# QI9-2604-A01.net
KiCad netlist of a schematic drawn in Altium Designer
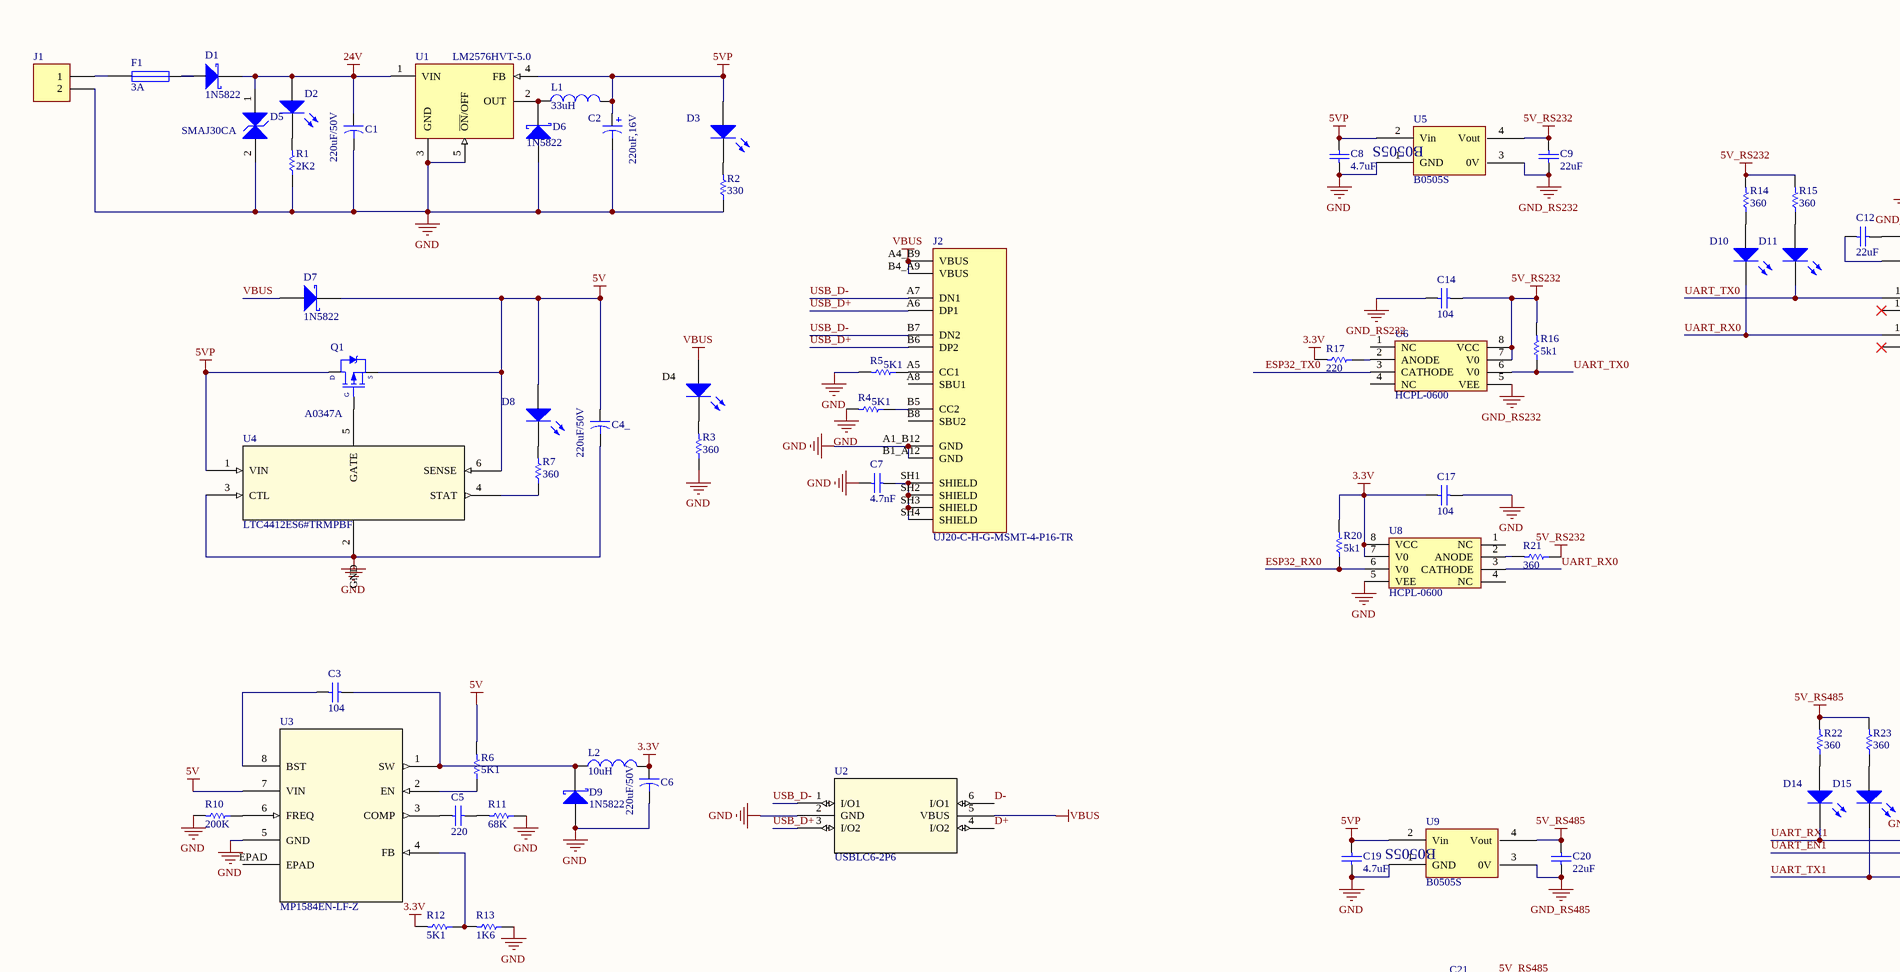
[diagram p0: QI9-2604-A01.SchDoc, top left]
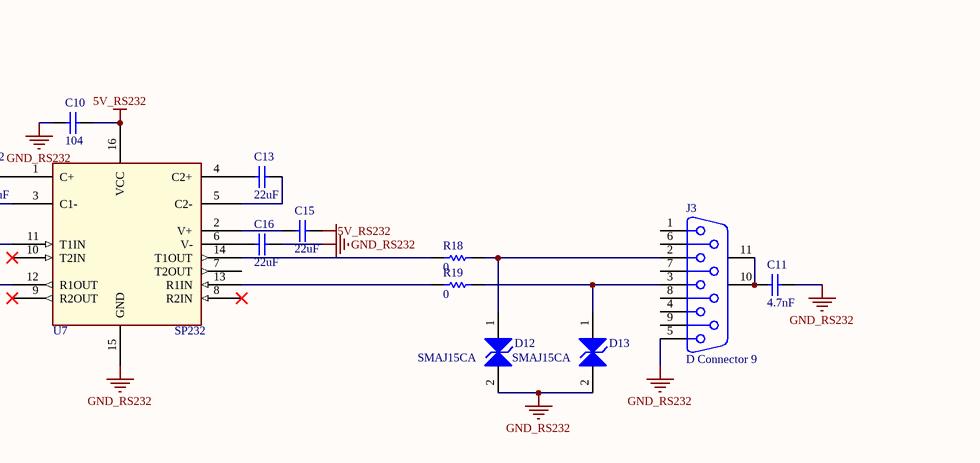
[diagram p1: QI9-2604-A01.SchDoc, top right]
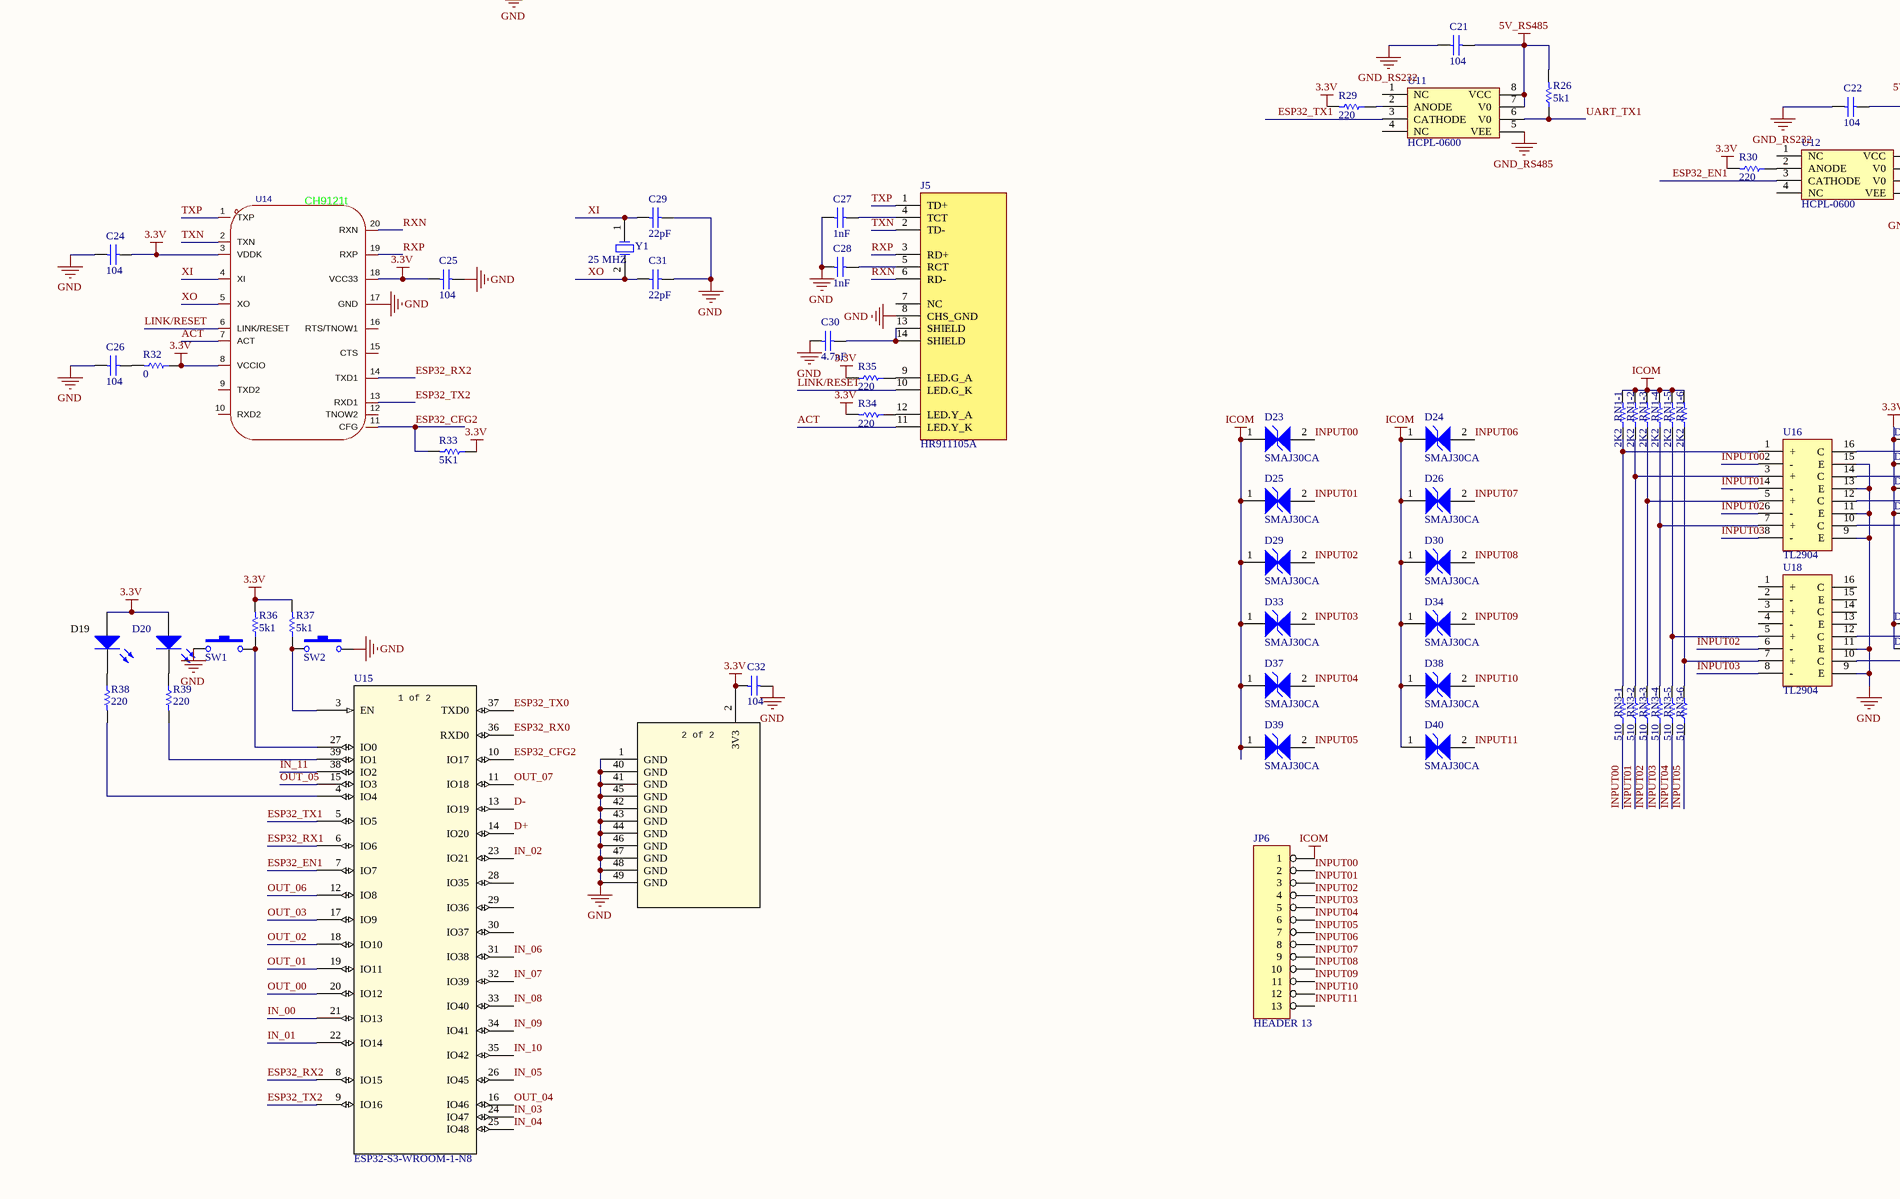
[diagram p2: QI9-2604-A01.SchDoc, bottom left]
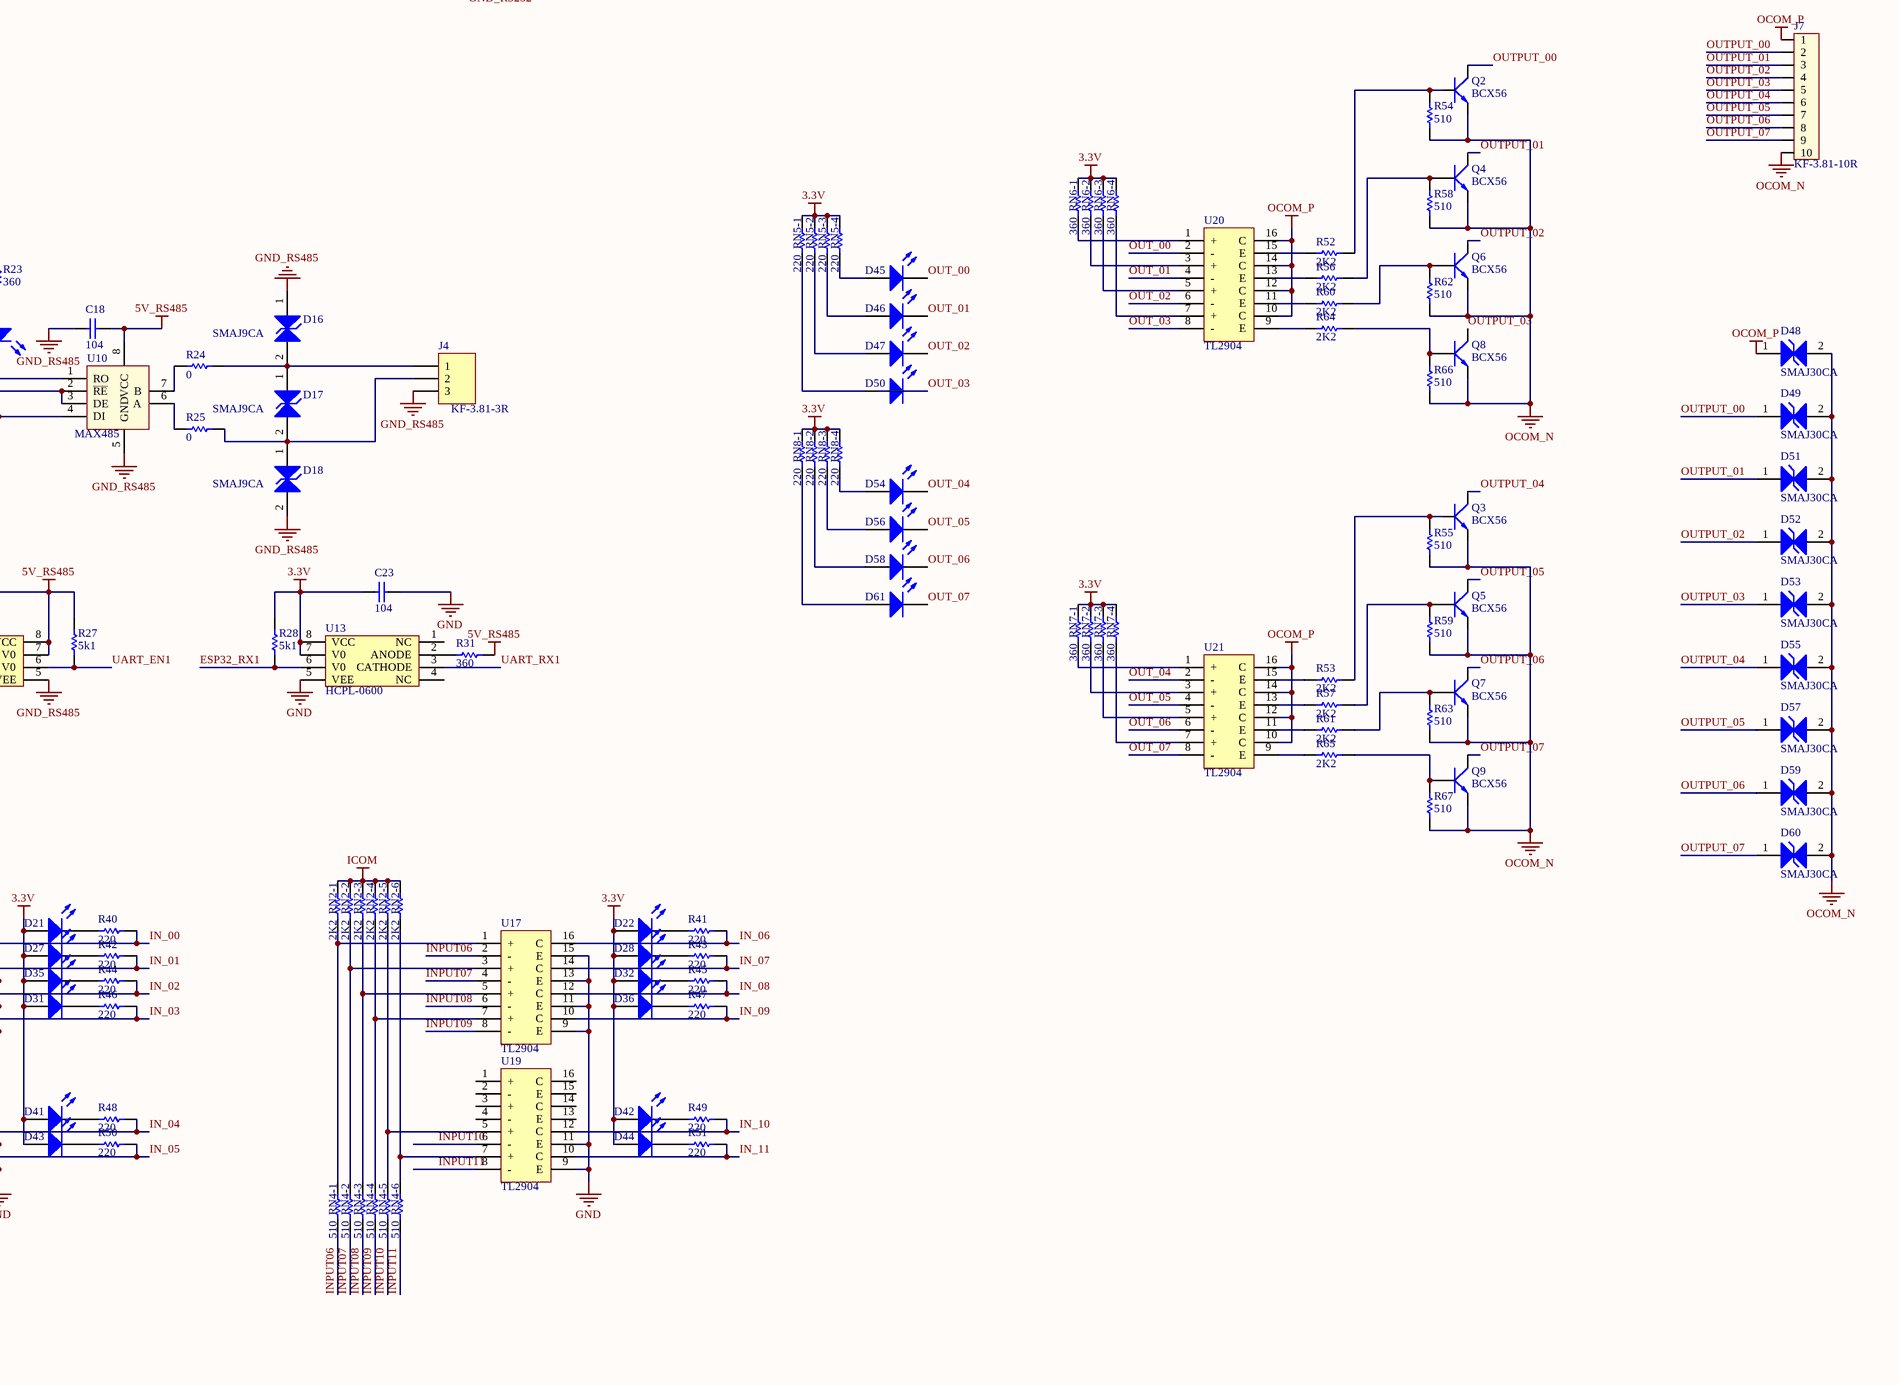
[diagram p3: QI9-2604-A01.SchDoc, bottom right]

(export (version "E")
  (design (tool "Eeschema 10.0.6"))
  (components
    (comp (ref "C1")
      (value "220uF/50V")
      (footprint "C2")
      (description "Capacitor")
      (fields (field (name "Comment") "Cap2") (field (name "PUBLISHER") "Altium Limited"))
      (libsource (lib "Miscellaneous Devices") (part "Cap2"))
    )
    (comp (ref "C2")
      (value "220uF,16V")
      (footprint "c3")
      (description "Polarized Capacitor (Axial)")
      (fields (field (name "PUBLISHER") "Altium Limited"))
      (libsource (lib "StandardLIB") (part "Cap Pol 3mm"))
    )
    (comp (ref "C3")
      (value "104")
      (footprint "0805")
      (description "Capacitor")
      (fields (field (name "Comment") "Cap") (field (name "PUBLISHER") "Altium Limited"))
      (libsource (lib "Miscellaneous Devices") (part "Cap"))
    )
    (comp (ref "C4_")
      (value "220uF/50V")
      (footprint "C2")
      (description "Capacitor")
      (fields (field (name "Comment") "Cap2") (field (name "PUBLISHER") "Altium Limited"))
      (libsource (lib "Miscellaneous Devices") (part "Cap2"))
    )
    (comp (ref "C5")
      (value "220")
      (footprint "0805")
      (description "Capacitor")
      (fields (field (name "Comment") "Cap") (field (name "PUBLISHER") "Altium Limited"))
      (libsource (lib "Miscellaneous Devices") (part "Cap"))
    )
    (comp (ref "C6")
      (value "220uF/50V")
      (footprint "C2")
      (description "Capacitor")
      (fields (field (name "Comment") "Cap2") (field (name "PUBLISHER") "Altium Limited"))
      (libsource (lib "Miscellaneous Devices") (part "Cap2"))
    )
    (comp (ref "C7")
      (value "4.7nF")
      (footprint "0805")
      (description "Capacitor")
      (fields (field (name "Comment") "Cap") (field (name "PUBLISHER") "Altium Limited"))
      (libsource (lib "Miscellaneous Devices") (part "Cap"))
    )
    (comp (ref "C8")
      (value "4.7uF")
      (footprint "0805")
      (description "Capacitor")
      (fields (field (name "Comment") "Cap") (field (name "PUBLISHER") "Altium Limited"))
      (libsource (lib "Miscellaneous Devices") (part "Cap"))
    )
    (comp (ref "C9")
      (value "22uF")
      (footprint "0805")
      (description "Capacitor")
      (fields (field (name "Comment") "Cap") (field (name "PUBLISHER") "Altium Limited"))
      (libsource (lib "Miscellaneous Devices") (part "Cap"))
    )
    (comp (ref "C10")
      (value "104")
      (footprint "0805")
      (description "Capacitor")
      (fields (field (name "Comment") "Cap") (field (name "PUBLISHER") "Altium Limited"))
      (libsource (lib "Miscellaneous Devices") (part "Cap"))
    )
    (comp (ref "C11")
      (value "4.7nF")
      (footprint "0805")
      (description "Capacitor")
      (fields (field (name "Comment") "Cap") (field (name "PUBLISHER") "Altium Limited"))
      (libsource (lib "Miscellaneous Devices") (part "Cap"))
    )
    (comp (ref "C12")
      (value "22uF")
      (footprint "0805")
      (description "Capacitor")
      (fields (field (name "Comment") "Cap") (field (name "PUBLISHER") "Altium Limited"))
      (libsource (lib "Miscellaneous Devices") (part "Cap"))
    )
    (comp (ref "C13")
      (value "22uF")
      (footprint "0805")
      (description "Capacitor")
      (fields (field (name "Comment") "Cap") (field (name "PUBLISHER") "Altium Limited"))
      (libsource (lib "Miscellaneous Devices") (part "Cap"))
    )
    (comp (ref "C14")
      (value "104")
      (footprint "0805")
      (description "Capacitor")
      (fields (field (name "Comment") "Cap") (field (name "PUBLISHER") "Altium Limited"))
      (libsource (lib "Miscellaneous Devices") (part "Cap"))
    )
    (comp (ref "C15")
      (value "22uF")
      (footprint "0805")
      (description "Capacitor")
      (fields (field (name "Comment") "Cap") (field (name "PUBLISHER") "Altium Limited"))
      (libsource (lib "Miscellaneous Devices") (part "Cap"))
    )
    (comp (ref "C16")
      (value "22uF")
      (footprint "0805")
      (description "Capacitor")
      (fields (field (name "Comment") "Cap") (field (name "PUBLISHER") "Altium Limited"))
      (libsource (lib "Miscellaneous Devices") (part "Cap"))
    )
    (comp (ref "C17")
      (value "104")
      (footprint "0805")
      (description "Capacitor")
      (fields (field (name "Comment") "Cap") (field (name "PUBLISHER") "Altium Limited"))
      (libsource (lib "Miscellaneous Devices") (part "Cap"))
    )
    (comp (ref "C18")
      (value "104")
      (footprint "0805")
      (description "Capacitor")
      (fields (field (name "Comment") "Cap") (field (name "PUBLISHER") "Altium Limited"))
      (libsource (lib "Miscellaneous Devices") (part "Cap"))
    )
    (comp (ref "C19")
      (value "4.7uF")
      (footprint "0805")
      (description "Capacitor")
      (fields (field (name "Comment") "Cap") (field (name "PUBLISHER") "Altium Limited"))
      (libsource (lib "Miscellaneous Devices") (part "Cap"))
    )
    (comp (ref "C20")
      (value "22uF")
      (footprint "0805")
      (description "Capacitor")
      (fields (field (name "Comment") "Cap") (field (name "PUBLISHER") "Altium Limited"))
      (libsource (lib "Miscellaneous Devices") (part "Cap"))
    )
    (comp (ref "C21")
      (value "104")
      (footprint "0805")
      (description "Capacitor")
      (fields (field (name "Comment") "Cap") (field (name "PUBLISHER") "Altium Limited"))
      (libsource (lib "Miscellaneous Devices") (part "Cap"))
    )
    (comp (ref "C22")
      (value "104")
      (footprint "0805")
      (description "Capacitor")
      (fields (field (name "Comment") "Cap") (field (name "PUBLISHER") "Altium Limited"))
      (libsource (lib "Miscellaneous Devices") (part "Cap"))
    )
    (comp (ref "C23")
      (value "104")
      (footprint "0805")
      (description "Capacitor")
      (fields (field (name "Comment") "Cap") (field (name "PUBLISHER") "Altium Limited"))
      (libsource (lib "Miscellaneous Devices") (part "Cap"))
    )
    (comp (ref "C24")
      (value "104")
      (footprint "0805")
      (description "Capacitor")
      (fields (field (name "Comment") "Cap") (field (name "PUBLISHER") "Altium Limited"))
      (libsource (lib "Miscellaneous Devices") (part "Cap"))
    )
    (comp (ref "C25")
      (value "104")
      (footprint "0805")
      (description "Capacitor")
      (fields (field (name "Comment") "Cap") (field (name "PUBLISHER") "Altium Limited"))
      (libsource (lib "Miscellaneous Devices") (part "Cap"))
    )
    (comp (ref "C26")
      (value "104")
      (footprint "0805")
      (description "Capacitor")
      (fields (field (name "Comment") "Cap") (field (name "PUBLISHER") "Altium Limited"))
      (libsource (lib "Miscellaneous Devices") (part "Cap"))
    )
    (comp (ref "C27")
      (value "1nF")
      (footprint "0805")
      (description "Capacitor")
      (fields (field (name "Comment") "Cap") (field (name "PUBLISHER") "Altium Limited"))
      (libsource (lib "Miscellaneous Devices") (part "Cap"))
    )
    (comp (ref "C28")
      (value "1nF")
      (footprint "0805")
      (description "Capacitor")
      (fields (field (name "Comment") "Cap") (field (name "PUBLISHER") "Altium Limited"))
      (libsource (lib "Miscellaneous Devices") (part "Cap"))
    )
    (comp (ref "C29")
      (value "22pF")
      (footprint "0805")
      (description "Capacitor")
      (fields (field (name "Comment") "Cap") (field (name "PUBLISHER") "Altium Limited"))
      (libsource (lib "Miscellaneous Devices") (part "Cap"))
    )
    (comp (ref "C30")
      (value "4.7nF")
      (footprint "0805")
      (description "Capacitor")
      (fields (field (name "Comment") "Cap") (field (name "PUBLISHER") "Altium Limited"))
      (libsource (lib "Miscellaneous Devices") (part "Cap"))
    )
    (comp (ref "C31")
      (value "22pF")
      (footprint "0805")
      (description "Capacitor")
      (fields (field (name "Comment") "Cap") (field (name "PUBLISHER") "Altium Limited"))
      (libsource (lib "Miscellaneous Devices") (part "Cap"))
    )
    (comp (ref "C32")
      (value "104")
      (footprint "0805")
      (description "Capacitor")
      (fields (field (name "Comment") "Cap") (field (name "PUBLISHER") "Altium Limited"))
      (libsource (lib "Miscellaneous Devices") (part "Cap"))
    )
    (comp (ref "D1")
      (value "1N5822")
      (footprint "DIODE_DO214AC_SMA")
      (description "Schottky Diode")
      (fields (field (name "PUBLISHER") "Altium Limited"))
      (libsource (lib "Miscellaneous Devices") (part "D Schottky"))
    )
    (comp (ref "D2")
      (value "LED")
      (footprint "LED_0805_RED")
      (description "Typical INFRARED GaAs LED")
      (fields (field (name "PUBLISHER") "Altium Limited"))
      (libsource (lib "Miscellaneous Devices") (part "LED0"))
    )
    (comp (ref "D3")
      (value "LED")
      (footprint "LED_0805_RED")
      (description "Typical INFRARED GaAs LED")
      (fields (field (name "PUBLISHER") "Altium Limited"))
      (libsource (lib "Miscellaneous Devices") (part "LED0"))
    )
    (comp (ref "D4")
      (value "LED")
      (footprint "LED_0805_RED")
      (description "Typical INFRARED GaAs LED")
      (fields (field (name "PUBLISHER") "Altium Limited"))
      (libsource (lib "Miscellaneous Devices") (part "LED0"))
    )
    (comp (ref "D5")
      (value "SMAJ30CA")
      (footprint "SMA_STM")
      (description "TVS DIODE 30V 48.4V DO214AC")
      (fields (field (name "MPN") "SMAJ30A") (field (name "MFR") "Littelfuse Inc."))
      (libsource (lib "Cty1") (part "SMAJ30CA"))
    )
    (comp (ref "D6")
      (value "1N5822")
      (footprint "DIODE_DO214AC_SMA")
      (description "Schottky Diode")
      (fields (field (name "PUBLISHER") "Altium Limited"))
      (libsource (lib "Miscellaneous Devices") (part "D Schottky"))
    )
    (comp (ref "D7")
      (value "1N5822")
      (footprint "DIODE_DO214AC_SMA")
      (description "Schottky Diode")
      (fields (field (name "PUBLISHER") "Altium Limited"))
      (libsource (lib "Miscellaneous Devices") (part "D Schottky"))
    )
    (comp (ref "D8")
      (value "LED")
      (footprint "LED_0805_RED")
      (description "Typical INFRARED GaAs LED")
      (fields (field (name "PUBLISHER") "Altium Limited"))
      (libsource (lib "Miscellaneous Devices") (part "LED0"))
    )
    (comp (ref "D9")
      (value "1N5822")
      (footprint "DIODE_DO214AC_SMA")
      (description "Schottky Diode")
      (fields (field (name "PUBLISHER") "Altium Limited"))
      (libsource (lib "Miscellaneous Devices") (part "D Schottky"))
    )
    (comp (ref "D10")
      (value "LED")
      (footprint "LED_0805_RED")
      (description "Typical INFRARED GaAs LED")
      (fields (field (name "PUBLISHER") "Altium Limited"))
      (libsource (lib "Miscellaneous Devices") (part "LED0"))
    )
    (comp (ref "D11")
      (value "LED")
      (footprint "LED_0805_RED")
      (description "Typical INFRARED GaAs LED")
      (fields (field (name "PUBLISHER") "Altium Limited"))
      (libsource (lib "Miscellaneous Devices") (part "LED0"))
    )
    (comp (ref "D12")
      (value "SMAJ15CA")
      (footprint "SMA_STM")
      (description "TVS DIODE 30V 48.4V DO214AC")
      (fields (field (name "MPN") "SMAJ30A") (field (name "MFR") "Littelfuse Inc."))
      (libsource (lib "Cty1") (part "SMAJ30CA"))
    )
    (comp (ref "D13")
      (value "SMAJ15CA")
      (footprint "SMA_STM")
      (description "TVS DIODE 30V 48.4V DO214AC")
      (fields (field (name "MPN") "SMAJ30A") (field (name "MFR") "Littelfuse Inc."))
      (libsource (lib "Cty1") (part "SMAJ30CA"))
    )
    (comp (ref "D14")
      (value "LED")
      (footprint "LED_0805_RED")
      (description "Typical INFRARED GaAs LED")
      (fields (field (name "PUBLISHER") "Altium Limited"))
      (libsource (lib "Miscellaneous Devices") (part "LED0"))
    )
    (comp (ref "D15")
      (value "LED")
      (footprint "LED_0805_RED")
      (description "Typical INFRARED GaAs LED")
      (fields (field (name "PUBLISHER") "Altium Limited"))
      (libsource (lib "Miscellaneous Devices") (part "LED0"))
    )
    (comp (ref "D16")
      (value "SMAJ9CA")
      (footprint "SMA_STM")
      (description "TVS DIODE 30V 48.4V DO214AC")
      (fields (field (name "MPN") "SMAJ30A") (field (name "MFR") "Littelfuse Inc."))
      (libsource (lib "Cty1") (part "SMAJ30CA"))
    )
    (comp (ref "D17")
      (value "SMAJ9CA")
      (footprint "SMA_STM")
      (description "TVS DIODE 30V 48.4V DO214AC")
      (fields (field (name "MPN") "SMAJ30A") (field (name "MFR") "Littelfuse Inc."))
      (libsource (lib "Cty1") (part "SMAJ30CA"))
    )
    (comp (ref "D18")
      (value "SMAJ9CA")
      (footprint "SMA_STM")
      (description "TVS DIODE 30V 48.4V DO214AC")
      (fields (field (name "MPN") "SMAJ30A") (field (name "MFR") "Littelfuse Inc."))
      (libsource (lib "Cty1") (part "SMAJ30CA"))
    )
    (comp (ref "D19")
      (value "LED")
      (footprint "LED_0805_RED")
      (description "Typical INFRARED GaAs LED")
      (fields (field (name "PUBLISHER") "Altium Limited"))
      (libsource (lib "Miscellaneous Devices") (part "LED0"))
    )
    (comp (ref "D20")
      (value "LED")
      (footprint "LED_0805_RED")
      (description "Typical INFRARED GaAs LED")
      (fields (field (name "PUBLISHER") "Altium Limited"))
      (libsource (lib "Miscellaneous Devices") (part "LED0"))
    )
    (comp (ref "D21")
      (value "LED")
      (footprint "LED_0805_RED")
      (description "Typical INFRARED GaAs LED")
      (fields (field (name "PUBLISHER") "Altium Limited"))
      (libsource (lib "Miscellaneous Devices") (part "LED0"))
    )
    (comp (ref "D22")
      (value "LED")
      (footprint "LED_0805_RED")
      (description "Typical INFRARED GaAs LED")
      (fields (field (name "PUBLISHER") "Altium Limited"))
      (libsource (lib "Miscellaneous Devices") (part "LED0"))
    )
    (comp (ref "D23")
      (value "SMAJ30CA")
      (footprint "SMA_STM")
      (description "TVS DIODE 30V 48.4V DO214AC")
      (fields (field (name "MPN") "SMAJ30A") (field (name "MFR") "Littelfuse Inc."))
      (libsource (lib "Cty1") (part "SMAJ30CA"))
    )
    (comp (ref "D24")
      (value "SMAJ30CA")
      (footprint "SMA_STM")
      (description "TVS DIODE 30V 48.4V DO214AC")
      (fields (field (name "MPN") "SMAJ30A") (field (name "MFR") "Littelfuse Inc."))
      (libsource (lib "Cty1") (part "SMAJ30CA"))
    )
    (comp (ref "D25")
      (value "SMAJ30CA")
      (footprint "SMA_STM")
      (description "TVS DIODE 30V 48.4V DO214AC")
      (fields (field (name "MPN") "SMAJ30A") (field (name "MFR") "Littelfuse Inc."))
      (libsource (lib "Cty1") (part "SMAJ30CA"))
    )
    (comp (ref "D26")
      (value "SMAJ30CA")
      (footprint "SMA_STM")
      (description "TVS DIODE 30V 48.4V DO214AC")
      (fields (field (name "MPN") "SMAJ30A") (field (name "MFR") "Littelfuse Inc."))
      (libsource (lib "Cty1") (part "SMAJ30CA"))
    )
    (comp (ref "D27")
      (value "LED")
      (footprint "LED_0805_RED")
      (description "Typical INFRARED GaAs LED")
      (fields (field (name "PUBLISHER") "Altium Limited"))
      (libsource (lib "Miscellaneous Devices") (part "LED0"))
    )
    (comp (ref "D28")
      (value "LED")
      (footprint "LED_0805_RED")
      (description "Typical INFRARED GaAs LED")
      (fields (field (name "PUBLISHER") "Altium Limited"))
      (libsource (lib "Miscellaneous Devices") (part "LED0"))
    )
    (comp (ref "D29")
      (value "SMAJ30CA")
      (footprint "SMA_STM")
      (description "TVS DIODE 30V 48.4V DO214AC")
      (fields (field (name "MPN") "SMAJ30A") (field (name "MFR") "Littelfuse Inc."))
      (libsource (lib "Cty1") (part "SMAJ30CA"))
    )
    (comp (ref "D30")
      (value "SMAJ30CA")
      (footprint "SMA_STM")
      (description "TVS DIODE 30V 48.4V DO214AC")
      (fields (field (name "MPN") "SMAJ30A") (field (name "MFR") "Littelfuse Inc."))
      (libsource (lib "Cty1") (part "SMAJ30CA"))
    )
    (comp (ref "D31")
      (value "LED")
      (footprint "LED_0805_RED")
      (description "Typical INFRARED GaAs LED")
      (fields (field (name "PUBLISHER") "Altium Limited"))
      (libsource (lib "Miscellaneous Devices") (part "LED0"))
    )
    (comp (ref "D32")
      (value "LED")
      (footprint "LED_0805_RED")
      (description "Typical INFRARED GaAs LED")
      (fields (field (name "PUBLISHER") "Altium Limited"))
      (libsource (lib "Miscellaneous Devices") (part "LED0"))
    )
    (comp (ref "D33")
      (value "SMAJ30CA")
      (footprint "SMA_STM")
      (description "TVS DIODE 30V 48.4V DO214AC")
      (fields (field (name "MPN") "SMAJ30A") (field (name "MFR") "Littelfuse Inc."))
      (libsource (lib "Cty1") (part "SMAJ30CA"))
    )
    (comp (ref "D34")
      (value "SMAJ30CA")
      (footprint "SMA_STM")
      (description "TVS DIODE 30V 48.4V DO214AC")
      (fields (field (name "MPN") "SMAJ30A") (field (name "MFR") "Littelfuse Inc."))
      (libsource (lib "Cty1") (part "SMAJ30CA"))
    )
    (comp (ref "D35")
      (value "LED")
      (footprint "LED_0805_RED")
      (description "Typical INFRARED GaAs LED")
      (fields (field (name "PUBLISHER") "Altium Limited"))
      (libsource (lib "Miscellaneous Devices") (part "LED0"))
    )
    (comp (ref "D36")
      (value "LED")
      (footprint "LED_0805_RED")
      (description "Typical INFRARED GaAs LED")
      (fields (field (name "PUBLISHER") "Altium Limited"))
      (libsource (lib "Miscellaneous Devices") (part "LED0"))
    )
    (comp (ref "D37")
      (value "SMAJ30CA")
      (footprint "SMA_STM")
      (description "TVS DIODE 30V 48.4V DO214AC")
      (fields (field (name "MPN") "SMAJ30A") (field (name "MFR") "Littelfuse Inc."))
      (libsource (lib "Cty1") (part "SMAJ30CA"))
    )
    (comp (ref "D38")
      (value "SMAJ30CA")
      (footprint "SMA_STM")
      (description "TVS DIODE 30V 48.4V DO214AC")
      (fields (field (name "MPN") "SMAJ30A") (field (name "MFR") "Littelfuse Inc."))
      (libsource (lib "Cty1") (part "SMAJ30CA"))
    )
    (comp (ref "D39")
      (value "SMAJ30CA")
      (footprint "SMA_STM")
      (description "TVS DIODE 30V 48.4V DO214AC")
      (fields (field (name "MPN") "SMAJ30A") (field (name "MFR") "Littelfuse Inc."))
      (libsource (lib "Cty1") (part "SMAJ30CA"))
    )
    (comp (ref "D40")
      (value "SMAJ30CA")
      (footprint "SMA_STM")
      (description "TVS DIODE 30V 48.4V DO214AC")
      (fields (field (name "MPN") "SMAJ30A") (field (name "MFR") "Littelfuse Inc."))
      (libsource (lib "Cty1") (part "SMAJ30CA"))
    )
    (comp (ref "D41")
      (value "LED")
      (footprint "LED_0805_RED")
      (description "Typical INFRARED GaAs LED")
      (fields (field (name "PUBLISHER") "Altium Limited"))
      (libsource (lib "Miscellaneous Devices") (part "LED0"))
    )
    (comp (ref "D42")
      (value "LED")
      (footprint "LED_0805_RED")
      (description "Typical INFRARED GaAs LED")
      (fields (field (name "PUBLISHER") "Altium Limited"))
      (libsource (lib "Miscellaneous Devices") (part "LED0"))
    )
    (comp (ref "D43")
      (value "LED")
      (footprint "LED_0805_RED")
      (description "Typical INFRARED GaAs LED")
      (fields (field (name "PUBLISHER") "Altium Limited"))
      (libsource (lib "Miscellaneous Devices") (part "LED0"))
    )
    (comp (ref "D44")
      (value "LED")
      (footprint "LED_0805_RED")
      (description "Typical INFRARED GaAs LED")
      (fields (field (name "PUBLISHER") "Altium Limited"))
      (libsource (lib "Miscellaneous Devices") (part "LED0"))
    )
    (comp (ref "D45")
      (value "LED")
      (footprint "LED_0805_RED")
      (description "Typical INFRARED GaAs LED")
      (fields (field (name "PUBLISHER") "Altium Limited"))
      (libsource (lib "Miscellaneous Devices") (part "LED0"))
    )
    (comp (ref "D46")
      (value "LED")
      (footprint "LED_0805_RED")
      (description "Typical INFRARED GaAs LED")
      (fields (field (name "PUBLISHER") "Altium Limited"))
      (libsource (lib "Miscellaneous Devices") (part "LED0"))
    )
    (comp (ref "D47")
      (value "LED")
      (footprint "LED_0805_RED")
      (description "Typical INFRARED GaAs LED")
      (fields (field (name "PUBLISHER") "Altium Limited"))
      (libsource (lib "Miscellaneous Devices") (part "LED0"))
    )
    (comp (ref "D48")
      (value "SMAJ30CA")
      (footprint "SMA_STM")
      (description "TVS DIODE 30V 48.4V DO214AC")
      (fields (field (name "MPN") "SMAJ30A") (field (name "MFR") "Littelfuse Inc."))
      (libsource (lib "Cty1") (part "SMAJ30CA"))
    )
    (comp (ref "D49")
      (value "SMAJ30CA")
      (footprint "SMA_STM")
      (description "TVS DIODE 30V 48.4V DO214AC")
      (fields (field (name "MPN") "SMAJ30A") (field (name "MFR") "Littelfuse Inc."))
      (libsource (lib "Cty1") (part "SMAJ30CA"))
    )
    (comp (ref "D50")
      (value "LED")
      (footprint "LED_0805_RED")
      (description "Typical INFRARED GaAs LED")
      (fields (field (name "PUBLISHER") "Altium Limited"))
      (libsource (lib "Miscellaneous Devices") (part "LED0"))
    )
    (comp (ref "D51")
      (value "SMAJ30CA")
      (footprint "SMA_STM")
      (description "TVS DIODE 30V 48.4V DO214AC")
      (fields (field (name "MPN") "SMAJ30A") (field (name "MFR") "Littelfuse Inc."))
      (libsource (lib "Cty1") (part "SMAJ30CA"))
    )
    (comp (ref "D52")
      (value "SMAJ30CA")
      (footprint "SMA_STM")
      (description "TVS DIODE 30V 48.4V DO214AC")
      (fields (field (name "MPN") "SMAJ30A") (field (name "MFR") "Littelfuse Inc."))
      (libsource (lib "Cty1") (part "SMAJ30CA"))
    )
    (comp (ref "D53")
      (value "SMAJ30CA")
      (footprint "SMA_STM")
      (description "TVS DIODE 30V 48.4V DO214AC")
      (fields (field (name "MPN") "SMAJ30A") (field (name "MFR") "Littelfuse Inc."))
      (libsource (lib "Cty1") (part "SMAJ30CA"))
    )
    (comp (ref "D54")
      (value "LED")
      (footprint "LED_0805_RED")
      (description "Typical INFRARED GaAs LED")
      (fields (field (name "PUBLISHER") "Altium Limited"))
      (libsource (lib "Miscellaneous Devices") (part "LED0"))
    )
    (comp (ref "D55")
      (value "SMAJ30CA")
      (footprint "SMA_STM")
      (description "TVS DIODE 30V 48.4V DO214AC")
      (fields (field (name "MPN") "SMAJ30A") (field (name "MFR") "Littelfuse Inc."))
      (libsource (lib "Cty1") (part "SMAJ30CA"))
    )
    (comp (ref "D56")
      (value "LED")
      (footprint "LED_0805_RED")
      (description "Typical INFRARED GaAs LED")
      (fields (field (name "PUBLISHER") "Altium Limited"))
      (libsource (lib "Miscellaneous Devices") (part "LED0"))
    )
    (comp (ref "D57")
      (value "SMAJ30CA")
      (footprint "SMA_STM")
      (description "TVS DIODE 30V 48.4V DO214AC")
      (fields (field (name "MPN") "SMAJ30A") (field (name "MFR") "Littelfuse Inc."))
      (libsource (lib "Cty1") (part "SMAJ30CA"))
    )
    (comp (ref "D58")
      (value "LED")
      (footprint "LED_0805_RED")
      (description "Typical INFRARED GaAs LED")
      (fields (field (name "PUBLISHER") "Altium Limited"))
      (libsource (lib "Miscellaneous Devices") (part "LED0"))
    )
    (comp (ref "D59")
      (value "SMAJ30CA")
      (footprint "SMA_STM")
      (description "TVS DIODE 30V 48.4V DO214AC")
      (fields (field (name "MPN") "SMAJ30A") (field (name "MFR") "Littelfuse Inc."))
      (libsource (lib "Cty1") (part "SMAJ30CA"))
    )
    (comp (ref "D60")
      (value "SMAJ30CA")
      (footprint "SMA_STM")
      (description "TVS DIODE 30V 48.4V DO214AC")
      (fields (field (name "MPN") "SMAJ30A") (field (name "MFR") "Littelfuse Inc."))
      (libsource (lib "Cty1") (part "SMAJ30CA"))
    )
    (comp (ref "D61")
      (value "LED")
      (footprint "LED_0805_RED")
      (description "Typical INFRARED GaAs LED")
      (fields (field (name "PUBLISHER") "Altium Limited"))
      (libsource (lib "Miscellaneous Devices") (part "LED0"))
    )
    (comp (ref "F1")
      (value "3A")
      (footprint "FUSE_1812(4532)")
      (description "Fuse")
      (fields (field (name "PUBLISHER") "Altium Limited"))
      (libsource (lib "Miscellaneous Devices") (part "Fuse 1"))
    )
    (comp (ref "J1")
      (value "KF-3.810-2R")
      (footprint "KF2-3.81")
      (description "Header, 2-Pin")
      (fields (field (name "PUBLISHER") "Altium Limited"))
      (libsource (lib "Miscellaneous Connectors") (part "Header 2"))
    )
    (comp (ref "J2")
      (value "UJ20-C-H-G-MSMT-4-P16-TR")
      (footprint "UJ20-C-H-G-MSMT-4-P16-TR")
      (fields (field (name "MF") "{'manufacturer': u'Same Sky (Formerly CUI Devices)'}"))
      (libsource (lib "Cty1") (part "UJ20-C-H-G-MSMT-4-P16-TR"))
    )
    (comp (ref "J3")
      (value "D Connector 9")
      (footprint "DSUB1.385-2H9")
      (description "Receptacle Assembly, 9 Position, Right Angle")
      (fields (field (name "PUBLISHER") "Altium Limited"))
      (libsource (lib "BYTECH_HW_LIB_2019 (1)") (part "DB9_RA"))
    )
    (comp (ref "J4")
      (value "KF-3.81-3R")
      (footprint "KF3-3.81")
      (description "Header, 3-Pin")
      (fields (field (name "PUBLISHER") "Altium Limited"))
      (libsource (lib "Miscellaneous Connectors") (part "Header 3"))
    )
    (comp (ref "J5")
      (value "HR911105A")
      (footprint "HR911105A")
      (description "Hanrun HR911105A RJ-45 Connector")
      (fields (field (name "MFR") "HanRun"))
      (libsource (lib "BYTECH_HW_LIB_2019 (1)") (part "HR911105A"))
    )
    (comp (ref "J7")
      (value "KF-3.81-10R")
      (footprint "KF10-3.81")
      (description "Connector 10")
      (libsource (lib "My Library") (part "Con10"))
    )
    (comp (ref "JP6") (value "HEADER 13") (footprint "kf13-3.81") (libsource (lib "Cty1") (part "HEADER 13")))
    (comp (ref "L1")
      (value "33uH")
      (footprint "L1A")
      (description "Inductor")
      (fields (field (name "PUBLISHER") "Altium Limited"))
      (libsource (lib "Miscellaneous Devices") (part "Inductor"))
    )
    (comp (ref "L2")
      (value "10uH")
      (footprint "L1A")
      (description "Inductor")
      (fields (field (name "PUBLISHER") "Altium Limited"))
      (libsource (lib "Miscellaneous Devices") (part "Inductor"))
    )
    (comp (ref "Q1")
      (value "A0347A")
      (footprint "SOT23_")
      (description "HEXFET P-Channel Power MOSFET")
      (fields (field (name "PUBLISHER") "Altium Limited"))
      (libsource (lib "Cty1") (part "IRF9540"))
    )
    (comp (ref "Q2")
      (value "BCX56")
      (footprint "SOT89")
      (description "NPN transistor")
      (libsource (lib "TranFet") (part "C1815 HF SMD"))
    )
    (comp (ref "Q3")
      (value "BCX56")
      (footprint "SOT89")
      (description "NPN transistor")
      (libsource (lib "TranFet") (part "C1815 HF SMD"))
    )
    (comp (ref "Q4")
      (value "BCX56")
      (footprint "SOT89")
      (description "NPN transistor")
      (libsource (lib "TranFet") (part "C1815 HF SMD"))
    )
    (comp (ref "Q5")
      (value "BCX56")
      (footprint "SOT89")
      (description "NPN transistor")
      (libsource (lib "TranFet") (part "C1815 HF SMD"))
    )
    (comp (ref "Q6")
      (value "BCX56")
      (footprint "SOT89")
      (description "NPN transistor")
      (libsource (lib "TranFet") (part "C1815 HF SMD"))
    )
    (comp (ref "Q7")
      (value "BCX56")
      (footprint "SOT89")
      (description "NPN transistor")
      (libsource (lib "TranFet") (part "C1815 HF SMD"))
    )
    (comp (ref "Q8")
      (value "BCX56")
      (footprint "SOT89")
      (description "NPN transistor")
      (libsource (lib "TranFet") (part "C1815 HF SMD"))
    )
    (comp (ref "Q9")
      (value "BCX56")
      (footprint "SOT89")
      (description "NPN transistor")
      (libsource (lib "TranFet") (part "C1815 HF SMD"))
    )
    (comp (ref "R1")
      (value "2K2")
      (footprint "SM-RES-0805")
      (description "Resistor")
      (fields (field (name "Comment") "Res1") (field (name "PUBLISHER") "Altium Limited"))
      (libsource (lib "Miscellaneous Devices") (part "Res1"))
    )
    (comp (ref "R2")
      (value "330")
      (footprint "SM-RES-0805")
      (description "Resistor")
      (fields (field (name "Comment") "Res1") (field (name "PUBLISHER") "Altium Limited"))
      (libsource (lib "Miscellaneous Devices") (part "Res1"))
    )
    (comp (ref "R3")
      (value "360")
      (footprint "SM-RES-0805")
      (description "Resistor")
      (fields (field (name "Comment") "Res1") (field (name "PUBLISHER") "Altium Limited"))
      (libsource (lib "Miscellaneous Devices") (part "Res1"))
    )
    (comp (ref "R4")
      (value "5K1")
      (footprint "SM-RES-0805")
      (description "Resistor")
      (fields (field (name "Comment") "Res1") (field (name "PUBLISHER") "Altium Limited"))
      (libsource (lib "Miscellaneous Devices") (part "Res1"))
    )
    (comp (ref "R5")
      (value "5K1")
      (footprint "SM-RES-0805")
      (description "Resistor")
      (fields (field (name "Comment") "Res1") (field (name "PUBLISHER") "Altium Limited"))
      (libsource (lib "Miscellaneous Devices") (part "Res1"))
    )
    (comp (ref "R6")
      (value "5K1")
      (footprint "SM-RES-0805")
      (description "Resistor")
      (fields (field (name "Comment") "Res1") (field (name "PUBLISHER") "Altium Limited"))
      (libsource (lib "Miscellaneous Devices") (part "Res1"))
    )
    (comp (ref "R7")
      (value "360")
      (footprint "SM-RES-0805")
      (description "Resistor")
      (fields (field (name "Comment") "Res1") (field (name "PUBLISHER") "Altium Limited"))
      (libsource (lib "Miscellaneous Devices") (part "Res1"))
    )
    (comp (ref "R10")
      (value "200K")
      (footprint "SM-RES-0805")
      (description "Resistor")
      (fields (field (name "Comment") "Res1") (field (name "PUBLISHER") "Altium Limited"))
      (libsource (lib "Miscellaneous Devices") (part "Res1"))
    )
    (comp (ref "R11")
      (value "68K")
      (footprint "SM-RES-0805")
      (description "Resistor")
      (fields (field (name "Comment") "Res1") (field (name "PUBLISHER") "Altium Limited"))
      (libsource (lib "Miscellaneous Devices") (part "Res1"))
    )
    (comp (ref "R12")
      (value "5K1")
      (footprint "SM-RES-0805")
      (description "Resistor")
      (fields (field (name "Comment") "Res1") (field (name "PUBLISHER") "Altium Limited"))
      (libsource (lib "Miscellaneous Devices") (part "Res1"))
    )
    (comp (ref "R13")
      (value "1K6")
      (footprint "SM-RES-0805")
      (description "Resistor")
      (fields (field (name "Comment") "Res1") (field (name "PUBLISHER") "Altium Limited"))
      (libsource (lib "Miscellaneous Devices") (part "Res1"))
    )
    (comp (ref "R14")
      (value "360")
      (footprint "SM-RES-0805")
      (description "Resistor")
      (fields (field (name "Comment") "Res1") (field (name "PUBLISHER") "Altium Limited"))
      (libsource (lib "Miscellaneous Devices") (part "Res1"))
    )
    (comp (ref "R15")
      (value "360")
      (footprint "SM-RES-0805")
      (description "Resistor")
      (fields (field (name "Comment") "Res1") (field (name "PUBLISHER") "Altium Limited"))
      (libsource (lib "Miscellaneous Devices") (part "Res1"))
    )
    (comp (ref "R16")
      (value "5k1")
      (footprint "SM-RES-0805")
      (description "Resistor")
      (fields (field (name "Comment") "Res1") (field (name "PUBLISHER") "Altium Limited"))
      (libsource (lib "Miscellaneous Devices") (part "Res1"))
    )
    (comp (ref "R17")
      (value "220")
      (footprint "SM-RES-0805")
      (description "Resistor")
      (fields (field (name "Comment") "Res1") (field (name "PUBLISHER") "Altium Limited"))
      (libsource (lib "Miscellaneous Devices") (part "Res1"))
    )
    (comp (ref "R18")
      (value "0")
      (footprint "SM-RES-0805")
      (description "Resistor")
      (fields (field (name "Comment") "Res1") (field (name "PUBLISHER") "Altium Limited"))
      (libsource (lib "Miscellaneous Devices") (part "Res1"))
    )
    (comp (ref "R19")
      (value "0")
      (footprint "SM-RES-0805")
      (description "Resistor")
      (fields (field (name "Comment") "Res1") (field (name "PUBLISHER") "Altium Limited"))
      (libsource (lib "Miscellaneous Devices") (part "Res1"))
    )
    (comp (ref "R20")
      (value "5k1")
      (footprint "SM-RES-0805")
      (description "Resistor")
      (fields (field (name "Comment") "Res1") (field (name "PUBLISHER") "Altium Limited"))
      (libsource (lib "Miscellaneous Devices") (part "Res1"))
    )
    (comp (ref "R21")
      (value "360")
      (footprint "SM-RES-0805")
      (description "Resistor")
      (fields (field (name "Comment") "Res1") (field (name "PUBLISHER") "Altium Limited"))
      (libsource (lib "Miscellaneous Devices") (part "Res1"))
    )
    (comp (ref "R22")
      (value "360")
      (footprint "SM-RES-0805")
      (description "Resistor")
      (fields (field (name "Comment") "Res1") (field (name "PUBLISHER") "Altium Limited"))
      (libsource (lib "Miscellaneous Devices") (part "Res1"))
    )
    (comp (ref "R23")
      (value "360")
      (footprint "SM-RES-0805")
      (description "Resistor")
      (fields (field (name "Comment") "Res1") (field (name "PUBLISHER") "Altium Limited"))
      (libsource (lib "Miscellaneous Devices") (part "Res1"))
    )
    (comp (ref "R24")
      (value "0")
      (footprint "SM-RES-0805")
      (description "Resistor")
      (fields (field (name "Comment") "Res1") (field (name "PUBLISHER") "Altium Limited"))
      (libsource (lib "Miscellaneous Devices") (part "Res1"))
    )
    (comp (ref "R25")
      (value "0")
      (footprint "SM-RES-0805")
      (description "Resistor")
      (fields (field (name "Comment") "Res1") (field (name "PUBLISHER") "Altium Limited"))
      (libsource (lib "Miscellaneous Devices") (part "Res1"))
    )
    (comp (ref "R26")
      (value "5k1")
      (footprint "SM-RES-0805")
      (description "Resistor")
      (fields (field (name "Comment") "Res1") (field (name "PUBLISHER") "Altium Limited"))
      (libsource (lib "Miscellaneous Devices") (part "Res1"))
    )
    (comp (ref "R27")
      (value "5k1")
      (footprint "SM-RES-0805")
      (description "Resistor")
      (fields (field (name "Comment") "Res1") (field (name "PUBLISHER") "Altium Limited"))
      (libsource (lib "Miscellaneous Devices") (part "Res1"))
    )
    (comp (ref "R28")
      (value "5k1")
      (footprint "SM-RES-0805")
      (description "Resistor")
      (fields (field (name "Comment") "Res1") (field (name "PUBLISHER") "Altium Limited"))
      (libsource (lib "Miscellaneous Devices") (part "Res1"))
    )
    (comp (ref "R29")
      (value "220")
      (footprint "SM-RES-0805")
      (description "Resistor")
      (fields (field (name "Comment") "Res1") (field (name "PUBLISHER") "Altium Limited"))
      (libsource (lib "Miscellaneous Devices") (part "Res1"))
    )
    (comp (ref "R30")
      (value "220")
      (footprint "SM-RES-0805")
      (description "Resistor")
      (fields (field (name "Comment") "Res1") (field (name "PUBLISHER") "Altium Limited"))
      (libsource (lib "Miscellaneous Devices") (part "Res1"))
    )
    (comp (ref "R31")
      (value "360")
      (footprint "SM-RES-0805")
      (description "Resistor")
      (fields (field (name "Comment") "Res1") (field (name "PUBLISHER") "Altium Limited"))
      (libsource (lib "Miscellaneous Devices") (part "Res1"))
    )
    (comp (ref "R32")
      (value "0")
      (footprint "SM-RES-0805")
      (description "Resistor")
      (fields (field (name "Comment") "Res1") (field (name "PUBLISHER") "Altium Limited"))
      (libsource (lib "Miscellaneous Devices") (part "Res1"))
    )
    (comp (ref "R33")
      (value "5K1")
      (footprint "SM-RES-0805")
      (description "Resistor")
      (fields (field (name "Comment") "Res1") (field (name "PUBLISHER") "Altium Limited"))
      (libsource (lib "Miscellaneous Devices") (part "Res1"))
    )
    (comp (ref "R34")
      (value "220")
      (footprint "SM-RES-0805")
      (description "Resistor")
      (fields (field (name "Comment") "Res1") (field (name "PUBLISHER") "Altium Limited"))
      (libsource (lib "Miscellaneous Devices") (part "Res1"))
    )
    (comp (ref "R35")
      (value "220")
      (footprint "SM-RES-0805")
      (description "Resistor")
      (fields (field (name "Comment") "Res1") (field (name "PUBLISHER") "Altium Limited"))
      (libsource (lib "Miscellaneous Devices") (part "Res1"))
    )
    (comp (ref "R36")
      (value "5k1")
      (footprint "SM-RES-0805")
      (description "Resistor")
      (fields (field (name "Comment") "Res1") (field (name "PUBLISHER") "Altium Limited"))
      (libsource (lib "Miscellaneous Devices") (part "Res1"))
    )
    (comp (ref "R37")
      (value "5k1")
      (footprint "SM-RES-0805")
      (description "Resistor")
      (fields (field (name "Comment") "Res1") (field (name "PUBLISHER") "Altium Limited"))
      (libsource (lib "Miscellaneous Devices") (part "Res1"))
    )
    (comp (ref "R38")
      (value "220")
      (footprint "SM-RES-0805")
      (description "Resistor")
      (fields (field (name "Comment") "Res1") (field (name "PUBLISHER") "Altium Limited"))
      (libsource (lib "Miscellaneous Devices") (part "Res1"))
    )
    (comp (ref "R39")
      (value "220")
      (footprint "SM-RES-0805")
      (description "Resistor")
      (fields (field (name "Comment") "Res1") (field (name "PUBLISHER") "Altium Limited"))
      (libsource (lib "Miscellaneous Devices") (part "Res1"))
    )
    (comp (ref "R40")
      (value "220")
      (footprint "SM-RES-0805")
      (description "Resistor")
      (fields (field (name "Comment") "Res1") (field (name "PUBLISHER") "Altium Limited"))
      (libsource (lib "Miscellaneous Devices") (part "Res1"))
    )
    (comp (ref "R41")
      (value "220")
      (footprint "SM-RES-0805")
      (description "Resistor")
      (fields (field (name "Comment") "Res1") (field (name "PUBLISHER") "Altium Limited"))
      (libsource (lib "Miscellaneous Devices") (part "Res1"))
    )
    (comp (ref "R42")
      (value "220")
      (footprint "SM-RES-0805")
      (description "Resistor")
      (fields (field (name "Comment") "Res1") (field (name "PUBLISHER") "Altium Limited"))
      (libsource (lib "Miscellaneous Devices") (part "Res1"))
    )
    (comp (ref "R43")
      (value "220")
      (footprint "SM-RES-0805")
      (description "Resistor")
      (fields (field (name "Comment") "Res1") (field (name "PUBLISHER") "Altium Limited"))
      (libsource (lib "Miscellaneous Devices") (part "Res1"))
    )
    (comp (ref "R44")
      (value "220")
      (footprint "SM-RES-0805")
      (description "Resistor")
      (fields (field (name "Comment") "Res1") (field (name "PUBLISHER") "Altium Limited"))
      (libsource (lib "Miscellaneous Devices") (part "Res1"))
    )
    (comp (ref "R45")
      (value "220")
      (footprint "SM-RES-0805")
      (description "Resistor")
      (fields (field (name "Comment") "Res1") (field (name "PUBLISHER") "Altium Limited"))
      (libsource (lib "Miscellaneous Devices") (part "Res1"))
    )
    (comp (ref "R46")
      (value "220")
      (footprint "SM-RES-0805")
      (description "Resistor")
      (fields (field (name "Comment") "Res1") (field (name "PUBLISHER") "Altium Limited"))
      (libsource (lib "Miscellaneous Devices") (part "Res1"))
    )
    (comp (ref "R47")
      (value "220")
      (footprint "SM-RES-0805")
      (description "Resistor")
      (fields (field (name "Comment") "Res1") (field (name "PUBLISHER") "Altium Limited"))
      (libsource (lib "Miscellaneous Devices") (part "Res1"))
    )
    (comp (ref "R48")
      (value "220")
      (footprint "SM-RES-0805")
      (description "Resistor")
      (fields (field (name "Comment") "Res1") (field (name "PUBLISHER") "Altium Limited"))
      (libsource (lib "Miscellaneous Devices") (part "Res1"))
    )
    (comp (ref "R49")
      (value "220")
      (footprint "SM-RES-0805")
      (description "Resistor")
      (fields (field (name "Comment") "Res1") (field (name "PUBLISHER") "Altium Limited"))
      (libsource (lib "Miscellaneous Devices") (part "Res1"))
    )
    (comp (ref "R50")
      (value "220")
      (footprint "SM-RES-0805")
      (description "Resistor")
      (fields (field (name "Comment") "Res1") (field (name "PUBLISHER") "Altium Limited"))
      (libsource (lib "Miscellaneous Devices") (part "Res1"))
    )
    (comp (ref "R51")
      (value "220")
      (footprint "SM-RES-0805")
      (description "Resistor")
      (fields (field (name "Comment") "Res1") (field (name "PUBLISHER") "Altium Limited"))
      (libsource (lib "Miscellaneous Devices") (part "Res1"))
    )
    (comp (ref "R52")
      (value "2K2")
      (footprint "SM-RES-0805")
      (description "Resistor")
      (fields (field (name "Comment") "Res1") (field (name "PUBLISHER") "Altium Limited"))
      (libsource (lib "Miscellaneous Devices") (part "Res1"))
    )
    (comp (ref "R53")
      (value "2K2")
      (footprint "SM-RES-0805")
      (description "Resistor")
      (fields (field (name "Comment") "Res1") (field (name "PUBLISHER") "Altium Limited"))
      (libsource (lib "Miscellaneous Devices") (part "Res1"))
    )
    (comp (ref "R54")
      (value "510")
      (footprint "SM-RES-0805")
      (description "Resistor")
      (fields (field (name "Comment") "Res1") (field (name "PUBLISHER") "Altium Limited"))
      (libsource (lib "Miscellaneous Devices") (part "Res1"))
    )
    (comp (ref "R55")
      (value "510")
      (footprint "SM-RES-0805")
      (description "Resistor")
      (fields (field (name "Comment") "Res1") (field (name "PUBLISHER") "Altium Limited"))
      (libsource (lib "Miscellaneous Devices") (part "Res1"))
    )
    (comp (ref "R56")
      (value "2K2")
      (footprint "SM-RES-0805")
      (description "Resistor")
      (fields (field (name "Comment") "Res1") (field (name "PUBLISHER") "Altium Limited"))
      (libsource (lib "Miscellaneous Devices") (part "Res1"))
    )
    (comp (ref "R57")
      (value "2K2")
      (footprint "SM-RES-0805")
      (description "Resistor")
      (fields (field (name "Comment") "Res1") (field (name "PUBLISHER") "Altium Limited"))
      (libsource (lib "Miscellaneous Devices") (part "Res1"))
    )
    (comp (ref "R58")
      (value "510")
      (footprint "SM-RES-0805")
      (description "Resistor")
      (fields (field (name "Comment") "Res1") (field (name "PUBLISHER") "Altium Limited"))
      (libsource (lib "Miscellaneous Devices") (part "Res1"))
    )
    (comp (ref "R59")
      (value "510")
      (footprint "SM-RES-0805")
      (description "Resistor")
      (fields (field (name "Comment") "Res1") (field (name "PUBLISHER") "Altium Limited"))
      (libsource (lib "Miscellaneous Devices") (part "Res1"))
    )
    (comp (ref "R60")
      (value "2K2")
      (footprint "SM-RES-0805")
      (description "Resistor")
      (fields (field (name "Comment") "Res1") (field (name "PUBLISHER") "Altium Limited"))
      (libsource (lib "Miscellaneous Devices") (part "Res1"))
    )
    (comp (ref "R61")
      (value "2K2")
      (footprint "SM-RES-0805")
      (description "Resistor")
      (fields (field (name "Comment") "Res1") (field (name "PUBLISHER") "Altium Limited"))
      (libsource (lib "Miscellaneous Devices") (part "Res1"))
    )
    (comp (ref "R62")
      (value "510")
      (footprint "SM-RES-0805")
      (description "Resistor")
      (fields (field (name "Comment") "Res1") (field (name "PUBLISHER") "Altium Limited"))
      (libsource (lib "Miscellaneous Devices") (part "Res1"))
    )
    (comp (ref "R63")
      (value "510")
      (footprint "SM-RES-0805")
      (description "Resistor")
      (fields (field (name "Comment") "Res1") (field (name "PUBLISHER") "Altium Limited"))
      (libsource (lib "Miscellaneous Devices") (part "Res1"))
    )
    (comp (ref "R64")
      (value "2K2")
      (footprint "SM-RES-0805")
      (description "Resistor")
      (fields (field (name "Comment") "Res1") (field (name "PUBLISHER") "Altium Limited"))
      (libsource (lib "Miscellaneous Devices") (part "Res1"))
    )
    (comp (ref "R65")
      (value "2K2")
      (footprint "SM-RES-0805")
      (description "Resistor")
      (fields (field (name "Comment") "Res1") (field (name "PUBLISHER") "Altium Limited"))
      (libsource (lib "Miscellaneous Devices") (part "Res1"))
    )
    (comp (ref "R66")
      (value "510")
      (footprint "SM-RES-0805")
      (description "Resistor")
      (fields (field (name "Comment") "Res1") (field (name "PUBLISHER") "Altium Limited"))
      (libsource (lib "Miscellaneous Devices") (part "Res1"))
    )
    (comp (ref "R67")
      (value "510")
      (footprint "SM-RES-0805")
      (description "Resistor")
      (fields (field (name "Comment") "Res1") (field (name "PUBLISHER") "Altium Limited"))
      (libsource (lib "Miscellaneous Devices") (part "Res1"))
    )
    (comp (ref "RN1-1")
      (value "2K2")
      (footprint "SM-RES-0805")
      (description "Resistor")
      (fields (field (name "Comment") "Res1") (field (name "PUBLISHER") "Altium Limited"))
      (libsource (lib "Miscellaneous Devices") (part "Res1"))
    )
    (comp (ref "RN1-2")
      (value "2K2")
      (footprint "SM-RES-0805")
      (description "Resistor")
      (fields (field (name "Comment") "Res1") (field (name "PUBLISHER") "Altium Limited"))
      (libsource (lib "Miscellaneous Devices") (part "Res1"))
    )
    (comp (ref "RN1-3")
      (value "2K2")
      (footprint "SM-RES-0805")
      (description "Resistor")
      (fields (field (name "Comment") "Res1") (field (name "PUBLISHER") "Altium Limited"))
      (libsource (lib "Miscellaneous Devices") (part "Res1"))
    )
    (comp (ref "RN1-4")
      (value "2K2")
      (footprint "SM-RES-0805")
      (description "Resistor")
      (fields (field (name "Comment") "Res1") (field (name "PUBLISHER") "Altium Limited"))
      (libsource (lib "Miscellaneous Devices") (part "Res1"))
    )
    (comp (ref "RN1-5")
      (value "2K2")
      (footprint "SM-RES-0805")
      (description "Resistor")
      (fields (field (name "Comment") "Res1") (field (name "PUBLISHER") "Altium Limited"))
      (libsource (lib "Miscellaneous Devices") (part "Res1"))
    )
    (comp (ref "RN1-6")
      (value "2K2")
      (footprint "SM-RES-0805")
      (description "Resistor")
      (fields (field (name "Comment") "Res1") (field (name "PUBLISHER") "Altium Limited"))
      (libsource (lib "Miscellaneous Devices") (part "Res1"))
    )
    (comp (ref "RN2-1")
      (value "2K2")
      (footprint "SM-RES-0805")
      (description "Resistor")
      (fields (field (name "Comment") "Res1") (field (name "PUBLISHER") "Altium Limited"))
      (libsource (lib "Miscellaneous Devices") (part "Res1"))
    )
    (comp (ref "RN2-2")
      (value "2K2")
      (footprint "SM-RES-0805")
      (description "Resistor")
      (fields (field (name "Comment") "Res1") (field (name "PUBLISHER") "Altium Limited"))
      (libsource (lib "Miscellaneous Devices") (part "Res1"))
    )
    (comp (ref "RN2-3")
      (value "2K2")
      (footprint "SM-RES-0805")
      (description "Resistor")
      (fields (field (name "Comment") "Res1") (field (name "PUBLISHER") "Altium Limited"))
      (libsource (lib "Miscellaneous Devices") (part "Res1"))
    )
    (comp (ref "RN2-4")
      (value "2K2")
      (footprint "SM-RES-0805")
      (description "Resistor")
      (fields (field (name "Comment") "Res1") (field (name "PUBLISHER") "Altium Limited"))
      (libsource (lib "Miscellaneous Devices") (part "Res1"))
    )
    (comp (ref "RN2-5")
      (value "2K2")
      (footprint "SM-RES-0805")
      (description "Resistor")
      (fields (field (name "Comment") "Res1") (field (name "PUBLISHER") "Altium Limited"))
      (libsource (lib "Miscellaneous Devices") (part "Res1"))
    )
    (comp (ref "RN2-6")
      (value "2K2")
      (footprint "SM-RES-0805")
      (description "Resistor")
      (fields (field (name "Comment") "Res1") (field (name "PUBLISHER") "Altium Limited"))
      (libsource (lib "Miscellaneous Devices") (part "Res1"))
    )
    (comp (ref "RN3-1")
      (value "510")
      (footprint "SM-RES-0805")
      (description "Resistor")
      (fields (field (name "Comment") "Res1") (field (name "PUBLISHER") "Altium Limited"))
      (libsource (lib "Miscellaneous Devices") (part "Res1"))
    )
    (comp (ref "RN3-2")
      (value "510")
      (footprint "SM-RES-0805")
      (description "Resistor")
      (fields (field (name "Comment") "Res1") (field (name "PUBLISHER") "Altium Limited"))
      (libsource (lib "Miscellaneous Devices") (part "Res1"))
    )
    (comp (ref "RN3-3")
      (value "510")
      (footprint "SM-RES-0805")
      (description "Resistor")
      (fields (field (name "Comment") "Res1") (field (name "PUBLISHER") "Altium Limited"))
      (libsource (lib "Miscellaneous Devices") (part "Res1"))
    )
    (comp (ref "RN3-4")
      (value "510")
      (footprint "SM-RES-0805")
      (description "Resistor")
      (fields (field (name "Comment") "Res1") (field (name "PUBLISHER") "Altium Limited"))
      (libsource (lib "Miscellaneous Devices") (part "Res1"))
    )
    (comp (ref "RN3-5")
      (value "510")
      (footprint "SM-RES-0805")
      (description "Resistor")
      (fields (field (name "Comment") "Res1") (field (name "PUBLISHER") "Altium Limited"))
      (libsource (lib "Miscellaneous Devices") (part "Res1"))
    )
    (comp (ref "RN3-6")
      (value "510")
      (footprint "SM-RES-0805")
      (description "Resistor")
      (fields (field (name "Comment") "Res1") (field (name "PUBLISHER") "Altium Limited"))
      (libsource (lib "Miscellaneous Devices") (part "Res1"))
    )
    (comp (ref "RN4-1")
      (value "510")
      (footprint "SM-RES-0805")
      (description "Resistor")
      (fields (field (name "Comment") "Res1") (field (name "PUBLISHER") "Altium Limited"))
      (libsource (lib "Miscellaneous Devices") (part "Res1"))
    )
    (comp (ref "RN4-2")
      (value "510")
      (footprint "SM-RES-0805")
      (description "Resistor")
      (fields (field (name "Comment") "Res1") (field (name "PUBLISHER") "Altium Limited"))
      (libsource (lib "Miscellaneous Devices") (part "Res1"))
    )
    (comp (ref "RN4-3")
      (value "510")
      (footprint "SM-RES-0805")
      (description "Resistor")
      (fields (field (name "Comment") "Res1") (field (name "PUBLISHER") "Altium Limited"))
      (libsource (lib "Miscellaneous Devices") (part "Res1"))
    )
    (comp (ref "RN4-4")
      (value "510")
      (footprint "SM-RES-0805")
      (description "Resistor")
      (fields (field (name "Comment") "Res1") (field (name "PUBLISHER") "Altium Limited"))
      (libsource (lib "Miscellaneous Devices") (part "Res1"))
    )
    (comp (ref "RN4-5")
      (value "510")
      (footprint "SM-RES-0805")
      (description "Resistor")
      (fields (field (name "Comment") "Res1") (field (name "PUBLISHER") "Altium Limited"))
      (libsource (lib "Miscellaneous Devices") (part "Res1"))
    )
    (comp (ref "RN4-6")
      (value "510")
      (footprint "SM-RES-0805")
      (description "Resistor")
      (fields (field (name "Comment") "Res1") (field (name "PUBLISHER") "Altium Limited"))
      (libsource (lib "Miscellaneous Devices") (part "Res1"))
    )
    (comp (ref "RN5-1")
      (value "220")
      (footprint "SM-RES-0805")
      (description "Resistor")
      (fields (field (name "Comment") "Res1") (field (name "PUBLISHER") "Altium Limited"))
      (libsource (lib "Miscellaneous Devices") (part "Res1"))
    )
    (comp (ref "RN5-2")
      (value "220")
      (footprint "SM-RES-0805")
      (description "Resistor")
      (fields (field (name "Comment") "Res1") (field (name "PUBLISHER") "Altium Limited"))
      (libsource (lib "Miscellaneous Devices") (part "Res1"))
    )
    (comp (ref "RN5-3")
      (value "220")
      (footprint "SM-RES-0805")
      (description "Resistor")
      (fields (field (name "Comment") "Res1") (field (name "PUBLISHER") "Altium Limited"))
      (libsource (lib "Miscellaneous Devices") (part "Res1"))
    )
    (comp (ref "RN5-4")
      (value "220")
      (footprint "SM-RES-0805")
      (description "Resistor")
      (fields (field (name "Comment") "Res1") (field (name "PUBLISHER") "Altium Limited"))
      (libsource (lib "Miscellaneous Devices") (part "Res1"))
    )
    (comp (ref "RN6-1")
      (value "360")
      (footprint "SM-RES-0805")
      (description "Resistor")
      (fields (field (name "Comment") "Res1") (field (name "PUBLISHER") "Altium Limited"))
      (libsource (lib "Miscellaneous Devices") (part "Res1"))
    )
    (comp (ref "RN6-2")
      (value "360")
      (footprint "SM-RES-0805")
      (description "Resistor")
      (fields (field (name "Comment") "Res1") (field (name "PUBLISHER") "Altium Limited"))
      (libsource (lib "Miscellaneous Devices") (part "Res1"))
    )
    (comp (ref "RN6-3")
      (value "360")
      (footprint "SM-RES-0805")
      (description "Resistor")
      (fields (field (name "Comment") "Res1") (field (name "PUBLISHER") "Altium Limited"))
      (libsource (lib "Miscellaneous Devices") (part "Res1"))
    )
    (comp (ref "RN6-4")
      (value "360")
      (footprint "SM-RES-0805")
      (description "Resistor")
      (fields (field (name "Comment") "Res1") (field (name "PUBLISHER") "Altium Limited"))
      (libsource (lib "Miscellaneous Devices") (part "Res1"))
    )
    (comp (ref "RN7-1")
      (value "360")
      (footprint "SM-RES-0805")
      (description "Resistor")
      (fields (field (name "Comment") "Res1") (field (name "PUBLISHER") "Altium Limited"))
      (libsource (lib "Miscellaneous Devices") (part "Res1"))
    )
    (comp (ref "RN7-2")
      (value "360")
      (footprint "SM-RES-0805")
      (description "Resistor")
      (fields (field (name "Comment") "Res1") (field (name "PUBLISHER") "Altium Limited"))
      (libsource (lib "Miscellaneous Devices") (part "Res1"))
    )
    (comp (ref "RN7-3")
      (value "360")
      (footprint "SM-RES-0805")
      (description "Resistor")
      (fields (field (name "Comment") "Res1") (field (name "PUBLISHER") "Altium Limited"))
      (libsource (lib "Miscellaneous Devices") (part "Res1"))
    )
    (comp (ref "RN7-4")
      (value "360")
      (footprint "SM-RES-0805")
      (description "Resistor")
      (fields (field (name "Comment") "Res1") (field (name "PUBLISHER") "Altium Limited"))
      (libsource (lib "Miscellaneous Devices") (part "Res1"))
    )
    (comp (ref "RN8-1")
      (value "220")
      (footprint "SM-RES-0805")
      (description "Resistor")
      (fields (field (name "Comment") "Res1") (field (name "PUBLISHER") "Altium Limited"))
      (libsource (lib "Miscellaneous Devices") (part "Res1"))
    )
    (comp (ref "RN8-2")
      (value "220")
      (footprint "SM-RES-0805")
      (description "Resistor")
      (fields (field (name "Comment") "Res1") (field (name "PUBLISHER") "Altium Limited"))
      (libsource (lib "Miscellaneous Devices") (part "Res1"))
    )
    (comp (ref "RN8-3")
      (value "220")
      (footprint "SM-RES-0805")
      (description "Resistor")
      (fields (field (name "Comment") "Res1") (field (name "PUBLISHER") "Altium Limited"))
      (libsource (lib "Miscellaneous Devices") (part "Res1"))
    )
    (comp (ref "RN8-4")
      (value "220")
      (footprint "SM-RES-0805")
      (description "Resistor")
      (fields (field (name "Comment") "Res1") (field (name "PUBLISHER") "Altium Limited"))
      (libsource (lib "Miscellaneous Devices") (part "Res1"))
    )
    (comp (ref "SW1")
      (value "SW-SMD")
      (footprint "SW-SMD")
      (description "Switch")
      (fields (field (name "PUBLISHER") "Altium Limited"))
      (libsource (lib "Cty1") (part "SW-SMD"))
    )
    (comp (ref "SW2")
      (value "SW-SMD")
      (footprint "SW-SMD")
      (description "Switch")
      (fields (field (name "PUBLISHER") "Altium Limited"))
      (libsource (lib "Cty1") (part "SW-SMD"))
    )
    (comp (ref "U1")
      (value "LM2576HVT-5.0")
      (footprint "T05")
      (description "SIMPLE SWITCHER; 3A Step-Down Voltage Regulator")
      (fields
        (field (name "MANUFACTURER") "National Semiconductor")
        (field (name "DIGIKEYPARTNUMBER") "LM2576HVT-5.0-ND")
        (field (name "PUBLISHER") "Altium Limited")
      )
      (libsource (lib "NSC Switcher") (part "LM2576HVT-5.0"))
    )
    (comp (ref "U2")
      (value "USBLC6-2P6")
      (footprint "SOT-666_STM")
      (description "ESD Protection for USB 2.0 High Speed")
      (fields (field (name "COPYRIGHT") "Copyright (C) 2025 Ultra Librarian. All rights reserved."))
      (libsource (lib "Cty1") (part "USBLC6-2P6"))
    )
    (comp (ref "U3")
      (value "MP1584EN-LF-Z")
      (footprint "SOIC8E_MPS")
      (description "<p>3A 1.5MHz 28V Step-Down Converter</p>")
      (fields (field (name "COPYRIGHT") "Copyright (C) 2026 Ultra Librarian. All rights reserved."))
      (libsource (lib "Cty1") (part "MP1584EN-LF-Z"))
    )
    (comp (ref "U4")
      (value "LTC4412ES6#TRMPBF")
      (footprint "SOT-6_S_LIT")
      (description "Low Loss PowerPathâ„¢ Controller in ThinSOT")
      (fields (field (name "COPYRIGHT") "Copyright (C) 2025 Ultra Librarian. All rights reserved."))
      (libsource (lib "Cty1") (part "LTC4412ES6TRMPBF"))
    )
    (comp (ref "U5")
      (value "B0505S")
      (footprint "B0505S")
      (description "Cắm")
      (libsource (lib "IC") (part "B0505S"))
    )
    (comp (ref "U6")
      (value "HCPL-0600")
      (footprint "SOIC8_50_328_25X90_SMT")
      (description "2.5A Gate Driver Optical Coupling 3750Vrms 1 Channel 8-DIP Gull Wing")
      (fields
        (field (name "MANUFACTURER") "Broadcom Avago")
        (field (name "MANUFACTURER PART NUMBER") "HCPL-3120-500E")
      )
      (libsource (lib "IC") (part "IC_HCPL-3120-500E"))
    )
    (comp (ref "U7")
      (value "SP232")
      (footprint "soic16_m")
      (description "Enhanced RS-232 Line Drivers/Receivers")
      (fields (field (name "MANUFACTURER") "Sipex") (field (name "PUBLISHER") "Hoang Nguyen"))
      (libsource (lib "hphonglib") (part "SP232"))
    )
    (comp (ref "U8")
      (value "HCPL-0600")
      (footprint "SOIC8_50_328_25X90_SMT")
      (description "2.5A Gate Driver Optical Coupling 3750Vrms 1 Channel 8-DIP Gull Wing")
      (fields
        (field (name "MANUFACTURER") "Broadcom Avago")
        (field (name "MANUFACTURER PART NUMBER") "HCPL-3120-500E")
      )
      (libsource (lib "") (part "IC_HCPL-3120-500E_1"))
    )
    (comp (ref "U9")
      (value "B0505S")
      (footprint "B0505S")
      (description "Cắm")
      (libsource (lib "IC") (part "B0505S"))
    )
    (comp (ref "U10")
      (value "MAX485")
      (footprint "DIP8")
      (description "RS232 - RS485 (Same sn75176)")
      (libsource (lib "altium-import") (part "root_0_MAX485_"))
    )
    (comp (ref "U11")
      (value "HCPL-0600")
      (footprint "SOIC8_50_328_25X90_SMT")
      (description "2.5A Gate Driver Optical Coupling 3750Vrms 1 Channel 8-DIP Gull Wing")
      (fields
        (field (name "MANUFACTURER") "Broadcom Avago")
        (field (name "MANUFACTURER PART NUMBER") "HCPL-3120-500E")
      )
      (libsource (lib "IC") (part "IC_HCPL-3120-500E"))
    )
    (comp (ref "U12")
      (value "HCPL-0600")
      (footprint "SOIC8_50_328_25X90_SMT")
      (description "2.5A Gate Driver Optical Coupling 3750Vrms 1 Channel 8-DIP Gull Wing")
      (fields
        (field (name "MANUFACTURER") "Broadcom Avago")
        (field (name "MANUFACTURER PART NUMBER") "HCPL-3120-500E")
      )
      (libsource (lib "IC") (part "IC_HCPL-3120-500E"))
    )
    (comp (ref "U13")
      (value "HCPL-0600")
      (footprint "SOIC8_50_328_25X90_SMT")
      (description "2.5A Gate Driver Optical Coupling 3750Vrms 1 Channel 8-DIP Gull Wing")
      (fields
        (field (name "MANUFACTURER") "Broadcom Avago")
        (field (name "MANUFACTURER PART NUMBER") "HCPL-3120-500E")
      )
      (libsource (lib "") (part "IC_HCPL-3120-500E_1"))
    )
    (comp (ref "U14")
      (value "CH9121t")
      (footprint "tssop20")
      (fields (field (name "MANUFACTURER") "WCH(南京沁恒)") (field (name "MANUFACTURERPART") "CH9121T"))
      (libsource (lib "altium-import") (part "root_0_ch9121t_c45354919_"))
    )
    (comp (ref "U15")
      (value "ESP32-S3-WROOM-1-N8")
      (footprint "ESP32-S3-WROOM-1_EXP")
      (description "Description")
      (fields (field (name "COPYRIGHT") "Copyright (C) 2026 Ultra Librarian. All rights reserved."))
      (libsource (lib "Cty1") (part "ESP32-S3-WROOM-1"))
    )
    (comp (ref "U16")
      (value "TL2904")
      (footprint "SOP16")
      (description "PC817 OPTO")
      (libsource (lib "Cty1") (part "PC817 x 4"))
    )
    (comp (ref "U17")
      (value "TL2904")
      (footprint "SOP16")
      (description "PC817 OPTO")
      (libsource (lib "Cty1") (part "PC817 x 4"))
    )
    (comp (ref "U18")
      (value "TL2904")
      (footprint "SOP16")
      (description "PC817 OPTO")
      (libsource (lib "Cty1") (part "PC817 x 4"))
    )
    (comp (ref "U19")
      (value "TL2904")
      (footprint "SOP16")
      (description "PC817 OPTO")
      (libsource (lib "Cty1") (part "PC817 x 4"))
    )
    (comp (ref "U20")
      (value "TL2904")
      (footprint "SOP16")
      (description "PC817 OPTO")
      (libsource (lib "Cty1") (part "PC817 x 4"))
    )
    (comp (ref "U21")
      (value "TL2904")
      (footprint "SOP16")
      (description "PC817 OPTO")
      (libsource (lib "Cty1") (part "PC817 x 4"))
    )
    (comp (ref "Y1")
      (value "25 MHZ")
      (footprint "CRYSTAL")
      (description "Crystal Oscillator")
      (fields (field (name "PUBLISHER") "Altium Limited"))
      (libsource (lib "Miscellaneous Devices") (part "XTAL"))
    )
  )
  (nets
    (net (code "1") (name "/ACT") (class "Default")
      (node (ref "J5") (pin "11") (pinfunction "LED.Y_K_11") (pintype "passive"))
      (node (ref "U14") (pin "7") (pinfunction "ACT_7") (pintype "passive"))
    )
    (net (code "2") (name "/D+") (class "Default")
      (node (ref "U15") (pin "14") (pinfunction "IO20_14") (pintype "bidirectional"))
      (node (ref "U2") (pin "4") (pinfunction "I/O2_4") (pintype "bidirectional"))
    )
    (net (code "3") (name "/D-") (class "Default")
      (node (ref "U15") (pin "13") (pinfunction "IO19_13") (pintype "bidirectional"))
      (node (ref "U2") (pin "6") (pinfunction "I/O1_6") (pintype "bidirectional"))
    )
    (net (code "4") (name "/ESP32_CFG2") (class "Default")
      (node (ref "R33") (pin "2") (pinfunction "2_2") (pintype "passive"))
      (node (ref "U14") (pin "11") (pinfunction "CFG_11") (pintype "passive"))
      (node (ref "U15") (pin "10") (pinfunction "IO17_10") (pintype "bidirectional"))
    )
    (net (code "5") (name "/ESP32_EN1") (class "Default")
      (node (ref "U12") (pin "3") (pinfunction "CATHODE_3") (pintype "passive"))
      (node (ref "U15") (pin "7") (pinfunction "IO7_7") (pintype "bidirectional"))
    )
    (net (code "6") (name "/ESP32_RX0") (class "Default")
      (node (ref "R20") (pin "1") (pinfunction "1_1") (pintype "passive"))
      (node (ref "U15") (pin "36") (pinfunction "RXD0_36") (pintype "bidirectional"))
      (node (ref "U8") (pin "6") (pinfunction "V0_6") (pintype "passive"))
    )
    (net (code "7") (name "/ESP32_RX1") (class "Default")
      (node (ref "R28") (pin "1") (pinfunction "1_1") (pintype "passive"))
      (node (ref "U13") (pin "6") (pinfunction "V0_6") (pintype "passive"))
      (node (ref "U15") (pin "6") (pinfunction "IO6_6") (pintype "bidirectional"))
    )
    (net (code "8") (name "/ESP32_RX2") (class "Default")
      (node (ref "U14") (pin "14") (pinfunction "TXD1_14") (pintype "passive"))
      (node (ref "U15") (pin "8") (pinfunction "IO15_8") (pintype "bidirectional"))
    )
    (net (code "9") (name "/ESP32_TX0") (class "Default")
      (node (ref "U15") (pin "37") (pinfunction "TXD0_37") (pintype "bidirectional"))
      (node (ref "U6") (pin "3") (pinfunction "CATHODE_3") (pintype "passive"))
    )
    (net (code "10") (name "/ESP32_TX1") (class "Default")
      (node (ref "U11") (pin "3") (pinfunction "CATHODE_3") (pintype "passive"))
      (node (ref "U15") (pin "5") (pinfunction "IO5_5") (pintype "bidirectional"))
    )
    (net (code "11") (name "/ESP32_TX2") (class "Default")
      (node (ref "U14") (pin "13") (pinfunction "RXD1_13") (pintype "passive"))
      (node (ref "U15") (pin "9") (pinfunction "IO16_9") (pintype "bidirectional"))
    )
    (net (code "12") (name "/INPUT00") (class "Default")
      (node (ref "D23") (pin "2") (pinfunction "K_2") (pintype "passive"))
      (node (ref "JP6") (pin "2") (pinfunction "2_2") (pintype "passive"))
      (node (ref "RN3-1") (pin "1") (pinfunction "1_1") (pintype "passive"))
      (node (ref "U16") (pin "2") (pinfunction "-_2") (pintype "passive"))
    )
    (net (code "13") (name "/INPUT01") (class "Default")
      (node (ref "D25") (pin "2") (pinfunction "K_2") (pintype "passive"))
      (node (ref "JP6") (pin "3") (pinfunction "3_3") (pintype "passive"))
      (node (ref "RN3-2") (pin "1") (pinfunction "1_1") (pintype "passive"))
      (node (ref "U16") (pin "4") (pinfunction "-_4") (pintype "passive"))
    )
    (net (code "14") (name "/INPUT02") (class "Default")
      (node (ref "D29") (pin "2") (pinfunction "K_2") (pintype "passive"))
      (node (ref "JP6") (pin "4") (pinfunction "4_4") (pintype "passive"))
      (node (ref "RN3-3") (pin "1") (pinfunction "1_1") (pintype "passive"))
      (node (ref "U16") (pin "6") (pinfunction "-_6") (pintype "passive"))
      (node (ref "U18") (pin "6") (pinfunction "-_6") (pintype "passive"))
    )
    (net (code "15") (name "/INPUT03") (class "Default")
      (node (ref "D33") (pin "2") (pinfunction "K_2") (pintype "passive"))
      (node (ref "JP6") (pin "5") (pinfunction "5_5") (pintype "passive"))
      (node (ref "RN3-4") (pin "1") (pinfunction "1_1") (pintype "passive"))
      (node (ref "U16") (pin "8") (pinfunction "-_8") (pintype "passive"))
      (node (ref "U18") (pin "8") (pinfunction "-_8") (pintype "passive"))
    )
    (net (code "16") (name "/INPUT04") (class "Default")
      (node (ref "D37") (pin "2") (pinfunction "K_2") (pintype "passive"))
      (node (ref "JP6") (pin "6") (pinfunction "6_6") (pintype "passive"))
      (node (ref "RN3-5") (pin "1") (pinfunction "1_1") (pintype "passive"))
    )
    (net (code "17") (name "/INPUT05") (class "Default")
      (node (ref "D39") (pin "2") (pinfunction "K_2") (pintype "passive"))
      (node (ref "JP6") (pin "7") (pinfunction "7_7") (pintype "passive"))
      (node (ref "RN3-6") (pin "1") (pinfunction "1_1") (pintype "passive"))
    )
    (net (code "18") (name "/INPUT06") (class "Default")
      (node (ref "D24") (pin "2") (pinfunction "K_2") (pintype "passive"))
      (node (ref "JP6") (pin "8") (pinfunction "8_8") (pintype "passive"))
      (node (ref "RN4-1") (pin "1") (pinfunction "1_1") (pintype "passive"))
      (node (ref "U17") (pin "2") (pinfunction "-_2") (pintype "passive"))
    )
    (net (code "19") (name "/INPUT07") (class "Default")
      (node (ref "D26") (pin "2") (pinfunction "K_2") (pintype "passive"))
      (node (ref "JP6") (pin "9") (pinfunction "9_9") (pintype "passive"))
      (node (ref "RN4-2") (pin "1") (pinfunction "1_1") (pintype "passive"))
      (node (ref "U17") (pin "4") (pinfunction "-_4") (pintype "passive"))
    )
    (net (code "20") (name "/INPUT08") (class "Default")
      (node (ref "D30") (pin "2") (pinfunction "K_2") (pintype "passive"))
      (node (ref "JP6") (pin "10") (pinfunction "10_10") (pintype "passive"))
      (node (ref "RN4-3") (pin "1") (pinfunction "1_1") (pintype "passive"))
      (node (ref "U17") (pin "6") (pinfunction "-_6") (pintype "passive"))
    )
    (net (code "21") (name "/INPUT09") (class "Default")
      (node (ref "D34") (pin "2") (pinfunction "K_2") (pintype "passive"))
      (node (ref "JP6") (pin "11") (pinfunction "11_11") (pintype "passive"))
      (node (ref "RN4-4") (pin "1") (pinfunction "1_1") (pintype "passive"))
      (node (ref "U17") (pin "8") (pinfunction "-_8") (pintype "passive"))
    )
    (net (code "22") (name "/INPUT10") (class "Default")
      (node (ref "D38") (pin "2") (pinfunction "K_2") (pintype "passive"))
      (node (ref "JP6") (pin "12") (pinfunction "12_12") (pintype "passive"))
      (node (ref "RN4-5") (pin "1") (pinfunction "1_1") (pintype "passive"))
      (node (ref "U19") (pin "6") (pinfunction "-_6") (pintype "passive"))
    )
    (net (code "23") (name "/INPUT11") (class "Default")
      (node (ref "D40") (pin "2") (pinfunction "K_2") (pintype "passive"))
      (node (ref "JP6") (pin "13") (pinfunction "13_13") (pintype "passive"))
      (node (ref "RN4-6") (pin "1") (pinfunction "1_1") (pintype "passive"))
      (node (ref "U19") (pin "8") (pinfunction "-_8") (pintype "passive"))
    )
    (net (code "24") (name "/IN_00") (class "Default")
      (node (ref "R40") (pin "2") (pinfunction "2_2") (pintype "passive"))
      (node (ref "U15") (pin "21") (pinfunction "IO13_21") (pintype "bidirectional"))
      (node (ref "U16") (pin "16") (pinfunction "C_16") (pintype "passive"))
    )
    (net (code "25") (name "/IN_01") (class "Default")
      (node (ref "R42") (pin "2") (pinfunction "2_2") (pintype "passive"))
      (node (ref "U15") (pin "22") (pinfunction "IO14_22") (pintype "bidirectional"))
      (node (ref "U16") (pin "14") (pinfunction "C_14") (pintype "passive"))
    )
    (net (code "26") (name "/IN_02") (class "Default")
      (node (ref "R44") (pin "2") (pinfunction "2_2") (pintype "passive"))
      (node (ref "U15") (pin "23") (pinfunction "IO21_23") (pintype "bidirectional"))
      (node (ref "U16") (pin "12") (pinfunction "C_12") (pintype "passive"))
    )
    (net (code "27") (name "/IN_03") (class "Default")
      (node (ref "R46") (pin "2") (pinfunction "2_2") (pintype "passive"))
      (node (ref "U15") (pin "24") (pinfunction "IO47_24") (pintype "bidirectional"))
      (node (ref "U16") (pin "10") (pinfunction "C_10") (pintype "passive"))
    )
    (net (code "28") (name "/IN_04") (class "Default")
      (node (ref "R48") (pin "2") (pinfunction "2_2") (pintype "passive"))
      (node (ref "U15") (pin "25") (pinfunction "IO48_25") (pintype "bidirectional"))
      (node (ref "U18") (pin "12") (pinfunction "C_12") (pintype "passive"))
    )
    (net (code "29") (name "/IN_05") (class "Default")
      (node (ref "R50") (pin "2") (pinfunction "2_2") (pintype "passive"))
      (node (ref "U15") (pin "26") (pinfunction "IO45_26") (pintype "bidirectional"))
      (node (ref "U18") (pin "10") (pinfunction "C_10") (pintype "passive"))
    )
    (net (code "30") (name "/IN_06") (class "Default")
      (node (ref "R41") (pin "2") (pinfunction "2_2") (pintype "passive"))
      (node (ref "U15") (pin "31") (pinfunction "IO38_31") (pintype "bidirectional"))
      (node (ref "U17") (pin "16") (pinfunction "C_16") (pintype "passive"))
    )
    (net (code "31") (name "/IN_07") (class "Default")
      (node (ref "R43") (pin "2") (pinfunction "2_2") (pintype "passive"))
      (node (ref "U15") (pin "32") (pinfunction "IO39_32") (pintype "bidirectional"))
      (node (ref "U17") (pin "14") (pinfunction "C_14") (pintype "passive"))
    )
    (net (code "32") (name "/IN_08") (class "Default")
      (node (ref "R45") (pin "2") (pinfunction "2_2") (pintype "passive"))
      (node (ref "U15") (pin "33") (pinfunction "IO40_33") (pintype "bidirectional"))
      (node (ref "U17") (pin "12") (pinfunction "C_12") (pintype "passive"))
    )
    (net (code "33") (name "/IN_09") (class "Default")
      (node (ref "R47") (pin "2") (pinfunction "2_2") (pintype "passive"))
      (node (ref "U15") (pin "34") (pinfunction "IO41_34") (pintype "bidirectional"))
      (node (ref "U17") (pin "10") (pinfunction "C_10") (pintype "passive"))
    )
    (net (code "34") (name "/IN_10") (class "Default")
      (node (ref "R49") (pin "2") (pinfunction "2_2") (pintype "passive"))
      (node (ref "U15") (pin "35") (pinfunction "IO42_35") (pintype "bidirectional"))
      (node (ref "U19") (pin "12") (pinfunction "C_12") (pintype "passive"))
    )
    (net (code "35") (name "/IN_11") (class "Default")
      (node (ref "R51") (pin "2") (pinfunction "2_2") (pintype "passive"))
      (node (ref "U15") (pin "38") (pinfunction "IO2_38") (pintype "bidirectional"))
      (node (ref "U19") (pin "10") (pinfunction "C_10") (pintype "passive"))
    )
    (net (code "36") (name "/LINK{slash}RESET") (class "Default")
      (node (ref "J5") (pin "10") (pinfunction "LED.G_K_10") (pintype "passive"))
      (node (ref "U14") (pin "6") (pinfunction "LINK/RESET_6") (pintype "passive"))
    )
    (net (code "37") (name "/OUTPUT_00") (class "Default")
      (node (ref "D49") (pin "1") (pinfunction "A_1") (pintype "passive"))
      (node (ref "J7") (pin "2") (pinfunction "2_2") (pintype "passive"))
      (node (ref "Q2") (pin "3") (pinfunction "C_3") (pintype "passive"))
    )
    (net (code "38") (name "/OUTPUT_01") (class "Default")
      (node (ref "D51") (pin "1") (pinfunction "A_1") (pintype "passive"))
      (node (ref "J7") (pin "3") (pinfunction "3_3") (pintype "passive"))
      (node (ref "Q4") (pin "3") (pinfunction "C_3") (pintype "passive"))
    )
    (net (code "39") (name "/OUTPUT_02") (class "Default")
      (node (ref "D52") (pin "1") (pinfunction "A_1") (pintype "passive"))
      (node (ref "J7") (pin "4") (pinfunction "4_4") (pintype "passive"))
      (node (ref "Q6") (pin "3") (pinfunction "C_3") (pintype "passive"))
    )
    (net (code "40") (name "/OUTPUT_03") (class "Default")
      (node (ref "D53") (pin "1") (pinfunction "A_1") (pintype "passive"))
      (node (ref "J7") (pin "5") (pinfunction "5_5") (pintype "passive"))
      (node (ref "Q8") (pin "3") (pinfunction "C_3") (pintype "passive"))
    )
    (net (code "41") (name "/OUTPUT_04") (class "Default")
      (node (ref "D55") (pin "1") (pinfunction "A_1") (pintype "passive"))
      (node (ref "J7") (pin "6") (pinfunction "6_6") (pintype "passive"))
      (node (ref "Q3") (pin "3") (pinfunction "C_3") (pintype "passive"))
    )
    (net (code "42") (name "/OUTPUT_05") (class "Default")
      (node (ref "D57") (pin "1") (pinfunction "A_1") (pintype "passive"))
      (node (ref "J7") (pin "7") (pinfunction "7_7") (pintype "passive"))
      (node (ref "Q5") (pin "3") (pinfunction "C_3") (pintype "passive"))
    )
    (net (code "43") (name "/OUTPUT_06") (class "Default")
      (node (ref "D59") (pin "1") (pinfunction "A_1") (pintype "passive"))
      (node (ref "J7") (pin "8") (pinfunction "8_8") (pintype "passive"))
      (node (ref "Q7") (pin "3") (pinfunction "C_3") (pintype "passive"))
    )
    (net (code "44") (name "/OUTPUT_07") (class "Default")
      (node (ref "D60") (pin "1") (pinfunction "A_1") (pintype "passive"))
      (node (ref "J7") (pin "9") (pinfunction "9_9") (pintype "passive"))
      (node (ref "Q9") (pin "3") (pinfunction "C_3") (pintype "passive"))
    )
    (net (code "45") (name "/OUT_00") (class "Default")
      (node (ref "D45") (pin "2") (pinfunction "K_2") (pintype "passive"))
      (node (ref "U15") (pin "20") (pinfunction "IO12_20") (pintype "bidirectional"))
      (node (ref "U20") (pin "2") (pinfunction "-_2") (pintype "passive"))
    )
    (net (code "46") (name "/OUT_01") (class "Default")
      (node (ref "D46") (pin "2") (pinfunction "K_2") (pintype "passive"))
      (node (ref "U15") (pin "19") (pinfunction "IO11_19") (pintype "bidirectional"))
      (node (ref "U20") (pin "4") (pinfunction "-_4") (pintype "passive"))
    )
    (net (code "47") (name "/OUT_02") (class "Default")
      (node (ref "D47") (pin "2") (pinfunction "K_2") (pintype "passive"))
      (node (ref "U15") (pin "18") (pinfunction "IO10_18") (pintype "bidirectional"))
      (node (ref "U20") (pin "6") (pinfunction "-_6") (pintype "passive"))
    )
    (net (code "48") (name "/OUT_03") (class "Default")
      (node (ref "D50") (pin "2") (pinfunction "K_2") (pintype "passive"))
      (node (ref "U15") (pin "17") (pinfunction "IO9_17") (pintype "bidirectional"))
      (node (ref "U20") (pin "8") (pinfunction "-_8") (pintype "passive"))
    )
    (net (code "49") (name "/OUT_04") (class "Default")
      (node (ref "D54") (pin "2") (pinfunction "K_2") (pintype "passive"))
      (node (ref "U15") (pin "16") (pinfunction "IO46_16") (pintype "bidirectional"))
      (node (ref "U21") (pin "2") (pinfunction "-_2") (pintype "passive"))
    )
    (net (code "50") (name "/OUT_05") (class "Default")
      (node (ref "D56") (pin "2") (pinfunction "K_2") (pintype "passive"))
      (node (ref "U15") (pin "15") (pinfunction "IO3_15") (pintype "bidirectional"))
      (node (ref "U21") (pin "4") (pinfunction "-_4") (pintype "passive"))
    )
    (net (code "51") (name "/OUT_06") (class "Default")
      (node (ref "D58") (pin "2") (pinfunction "K_2") (pintype "passive"))
      (node (ref "U15") (pin "12") (pinfunction "IO8_12") (pintype "bidirectional"))
      (node (ref "U21") (pin "6") (pinfunction "-_6") (pintype "passive"))
    )
    (net (code "52") (name "/OUT_07") (class "Default")
      (node (ref "D61") (pin "2") (pinfunction "K_2") (pintype "passive"))
      (node (ref "U15") (pin "11") (pinfunction "IO18_11") (pintype "bidirectional"))
      (node (ref "U21") (pin "8") (pinfunction "-_8") (pintype "passive"))
    )
    (net (code "53") (name "/RXN") (class "Default")
      (node (ref "J5") (pin "6") (pinfunction "RD-_6") (pintype "passive"))
      (node (ref "U14") (pin "20") (pinfunction "RXN_20") (pintype "passive"))
    )
    (net (code "54") (name "/RXP") (class "Default")
      (node (ref "J5") (pin "3") (pinfunction "RD+_3") (pintype "passive"))
      (node (ref "U14") (pin "19") (pinfunction "RXP_19") (pintype "passive"))
    )
    (net (code "55") (name "/TXN") (class "Default")
      (node (ref "J5") (pin "2") (pinfunction "TD-_2") (pintype "passive"))
      (node (ref "U14") (pin "2") (pinfunction "TXN_2") (pintype "passive"))
    )
    (net (code "56") (name "/TXP") (class "Default")
      (node (ref "J5") (pin "1") (pinfunction "TD+_1") (pintype "passive"))
      (node (ref "U14") (pin "1") (pinfunction "TXP_1") (pintype "passive"))
    )
    (net (code "57") (name "/UART_EN1") (class "Default")
      (node (ref "R27") (pin "1") (pinfunction "1_1") (pintype "passive"))
      (node (ref "U10") (pin "2") (pinfunction "~{RE}_2") (pintype "passive"))
      (node (ref "U10") (pin "3") (pinfunction "DE_3") (pintype "passive"))
      (node (ref "U12") (pin "6") (pinfunction "V0_6") (pintype "passive"))
    )
    (net (code "58") (name "/UART_RX0") (class "Default")
      (node (ref "D10") (pin "2") (pinfunction "K_2") (pintype "passive"))
      (node (ref "U7") (pin "12") (pinfunction "R1OUT_12") (pintype "output"))
      (node (ref "U8") (pin "3") (pinfunction "CATHODE_3") (pintype "passive"))
    )
    (net (code "59") (name "/UART_RX1") (class "Default")
      (node (ref "D14") (pin "2") (pinfunction "K_2") (pintype "passive"))
      (node (ref "U10") (pin "1") (pinfunction "RO_1") (pintype "passive"))
      (node (ref "U13") (pin "3") (pinfunction "CATHODE_3") (pintype "passive"))
    )
    (net (code "60") (name "/UART_TX0") (class "Default")
      (node (ref "D11") (pin "2") (pinfunction "K_2") (pintype "passive"))
      (node (ref "R16") (pin "1") (pinfunction "1_1") (pintype "passive"))
      (node (ref "U6") (pin "6") (pinfunction "V0_6") (pintype "passive"))
      (node (ref "U7") (pin "11") (pinfunction "T1IN_11") (pintype "input"))
    )
    (net (code "61") (name "/UART_TX1") (class "Default")
      (node (ref "D15") (pin "2") (pinfunction "K_2") (pintype "passive"))
      (node (ref "R26") (pin "1") (pinfunction "1_1") (pintype "passive"))
      (node (ref "U10") (pin "4") (pinfunction "DI_4") (pintype "passive"))
      (node (ref "U11") (pin "6") (pinfunction "V0_6") (pintype "passive"))
    )
    (net (code "62") (name "/USB_D+") (class "Default")
      (node (ref "J2") (pin "A6") (pinfunction "DP1_A6") (pintype "passive"))
      (node (ref "J2") (pin "B6") (pinfunction "DP2_B6") (pintype "passive"))
      (node (ref "U2") (pin "3") (pinfunction "I/O2_3") (pintype "bidirectional"))
    )
    (net (code "63") (name "/USB_D-") (class "Default")
      (node (ref "J2") (pin "A7") (pinfunction "DN1_A7") (pintype "passive"))
      (node (ref "J2") (pin "B7") (pinfunction "DN2_B7") (pintype "passive"))
      (node (ref "U2") (pin "1") (pinfunction "I/O1_1") (pintype "bidirectional"))
    )
    (net (code "64") (name "/XI") (class "Default")
      (node (ref "C29") (pin "1") (pinfunction "1_1") (pintype "passive"))
      (node (ref "U14") (pin "4") (pinfunction "XI_4") (pintype "passive"))
      (node (ref "Y1") (pin "1") (pinfunction "OSC1_1") (pintype "passive"))
    )
    (net (code "65") (name "/XO") (class "Default")
      (node (ref "C31") (pin "1") (pinfunction "1_1") (pintype "passive"))
      (node (ref "U14") (pin "5") (pinfunction "XO_5") (pintype "passive"))
      (node (ref "Y1") (pin "2") (pinfunction "OSC2_2") (pintype "passive"))
    )
    (net (code "66") (name "3.3V") (class "Default")
      (node (ref "C17") (pin "1") (pinfunction "1_1") (pintype "passive"))
      (node (ref "C23") (pin "1") (pinfunction "1_1") (pintype "passive"))
      (node (ref "C24") (pin "2") (pinfunction "2_2") (pintype "passive"))
      (node (ref "C25") (pin "1") (pinfunction "1_1") (pintype "passive"))
      (node (ref "C32") (pin "1") (pinfunction "1_1") (pintype "passive"))
      (node (ref "C6") (pin "1") (pinfunction "1_1") (pintype "passive"))
      (node (ref "D19") (pin "1") (pinfunction "A_1") (pintype "passive"))
      (node (ref "D20") (pin "1") (pinfunction "A_1") (pintype "passive"))
      (node (ref "D21") (pin "1") (pinfunction "A_1") (pintype "passive"))
      (node (ref "D22") (pin "1") (pinfunction "A_1") (pintype "passive"))
      (node (ref "D27") (pin "1") (pinfunction "A_1") (pintype "passive"))
      (node (ref "D28") (pin "1") (pinfunction "A_1") (pintype "passive"))
      (node (ref "D31") (pin "1") (pinfunction "A_1") (pintype "passive"))
      (node (ref "D32") (pin "1") (pinfunction "A_1") (pintype "passive"))
      (node (ref "D35") (pin "1") (pinfunction "A_1") (pintype "passive"))
      (node (ref "D36") (pin "1") (pinfunction "A_1") (pintype "passive"))
      (node (ref "D41") (pin "1") (pinfunction "A_1") (pintype "passive"))
      (node (ref "D42") (pin "1") (pinfunction "A_1") (pintype "passive"))
      (node (ref "D43") (pin "1") (pinfunction "A_1") (pintype "passive"))
      (node (ref "D44") (pin "1") (pinfunction "A_1") (pintype "passive"))
      (node (ref "L2") (pin "2") (pinfunction "2_2") (pintype "passive"))
      (node (ref "R12") (pin "2") (pinfunction "2_2") (pintype "passive"))
      (node (ref "R17") (pin "2") (pinfunction "2_2") (pintype "passive"))
      (node (ref "R20") (pin "2") (pinfunction "2_2") (pintype "passive"))
      (node (ref "R28") (pin "2") (pinfunction "2_2") (pintype "passive"))
      (node (ref "R29") (pin "2") (pinfunction "2_2") (pintype "passive"))
      (node (ref "R30") (pin "2") (pinfunction "2_2") (pintype "passive"))
      (node (ref "R32") (pin "1") (pinfunction "1_1") (pintype "passive"))
      (node (ref "R33") (pin "1") (pinfunction "1_1") (pintype "passive"))
      (node (ref "R34") (pin "2") (pinfunction "2_2") (pintype "passive"))
      (node (ref "R35") (pin "2") (pinfunction "2_2") (pintype "passive"))
      (node (ref "R36") (pin "2") (pinfunction "2_2") (pintype "passive"))
      (node (ref "R37") (pin "2") (pinfunction "2_2") (pintype "passive"))
      (node (ref "RN5-1") (pin "2") (pinfunction "2_2") (pintype "passive"))
      (node (ref "RN5-2") (pin "2") (pinfunction "2_2") (pintype "passive"))
      (node (ref "RN5-3") (pin "2") (pinfunction "2_2") (pintype "passive"))
      (node (ref "RN5-4") (pin "2") (pinfunction "2_2") (pintype "passive"))
      (node (ref "RN6-1") (pin "2") (pinfunction "2_2") (pintype "passive"))
      (node (ref "RN6-2") (pin "2") (pinfunction "2_2") (pintype "passive"))
      (node (ref "RN6-3") (pin "2") (pinfunction "2_2") (pintype "passive"))
      (node (ref "RN6-4") (pin "2") (pinfunction "2_2") (pintype "passive"))
      (node (ref "RN7-1") (pin "2") (pinfunction "2_2") (pintype "passive"))
      (node (ref "RN7-2") (pin "2") (pinfunction "2_2") (pintype "passive"))
      (node (ref "RN7-3") (pin "2") (pinfunction "2_2") (pintype "passive"))
      (node (ref "RN7-4") (pin "2") (pinfunction "2_2") (pintype "passive"))
      (node (ref "RN8-1") (pin "2") (pinfunction "2_2") (pintype "passive"))
      (node (ref "RN8-2") (pin "2") (pinfunction "2_2") (pintype "passive"))
      (node (ref "RN8-3") (pin "2") (pinfunction "2_2") (pintype "passive"))
      (node (ref "RN8-4") (pin "2") (pinfunction "2_2") (pintype "passive"))
      (node (ref "U13") (pin "7") (pinfunction "V0_7") (pintype "passive"))
      (node (ref "U13") (pin "8") (pinfunction "VCC_8") (pintype "passive"))
      (node (ref "U14") (pin "18") (pinfunction "VCC33_18") (pintype "passive"))
      (node (ref "U14") (pin "3") (pinfunction "VDDK_3") (pintype "passive"))
      (node (ref "U14") (pin "8") (pinfunction "VCCIO_8") (pintype "passive"))
      (node (ref "U15") (pin "2") (pinfunction "3V3_2") (pintype "power_in"))
      (node (ref "U8") (pin "7") (pinfunction "V0_7") (pintype "passive"))
      (node (ref "U8") (pin "8") (pinfunction "VCC_8") (pintype "passive"))
    )
    (net (code "67") (name "5V") (class "Default")
      (node (ref "C4_") (pin "1") (pinfunction "1_1") (pintype "passive"))
      (node (ref "D7") (pin "2") (pinfunction "K_2") (pintype "passive"))
      (node (ref "D8") (pin "1") (pinfunction "A_1") (pintype "passive"))
      (node (ref "Q1") (pin "3") (pinfunction "S_3") (pintype "passive"))
      (node (ref "R6") (pin "2") (pinfunction "2_2") (pintype "passive"))
      (node (ref "U3") (pin "7") (pinfunction "VIN_7") (pintype "power_in"))
      (node (ref "U4") (pin "6") (pinfunction "SENSE_6") (pintype "input"))
    )
    (net (code "68") (name "5VP") (class "Default")
      (node (ref "C19") (pin "1") (pinfunction "1_1") (pintype "passive"))
      (node (ref "C2") (pin "1") (pinfunction "1_1") (pintype "passive"))
      (node (ref "C8") (pin "1") (pinfunction "1_1") (pintype "passive"))
      (node (ref "D3") (pin "1") (pinfunction "A_1") (pintype "passive"))
      (node (ref "L1") (pin "2") (pinfunction "2_2") (pintype "passive"))
      (node (ref "Q1") (pin "2") (pinfunction "D_2") (pintype "passive"))
      (node (ref "U1") (pin "4") (pinfunction "FB_4") (pintype "input"))
      (node (ref "U4") (pin "1") (pinfunction "VIN_1") (pintype "input"))
      (node (ref "U5") (pin "2") (pinfunction "Vin_2") (pintype "passive"))
      (node (ref "U9") (pin "2") (pinfunction "Vin_2") (pintype "passive"))
    )
    (net (code "69") (name "5V_RS232") (class "Default")
      (node (ref "C10") (pin "2") (pinfunction "2_2") (pintype "passive"))
      (node (ref "C14") (pin "2") (pinfunction "2_2") (pintype "passive"))
      (node (ref "C15") (pin "2") (pinfunction "2_2") (pintype "passive"))
      (node (ref "C9") (pin "2") (pinfunction "2_2") (pintype "passive"))
      (node (ref "R14") (pin "2") (pinfunction "2_2") (pintype "passive"))
      (node (ref "R15") (pin "2") (pinfunction "2_2") (pintype "passive"))
      (node (ref "R16") (pin "2") (pinfunction "2_2") (pintype "passive"))
      (node (ref "R21") (pin "1") (pinfunction "1_1") (pintype "passive"))
      (node (ref "U5") (pin "4") (pinfunction "Vout_4") (pintype "passive"))
      (node (ref "U6") (pin "7") (pinfunction "V0_7") (pintype "passive"))
      (node (ref "U6") (pin "8") (pinfunction "VCC_8") (pintype "passive"))
      (node (ref "U7") (pin "16") (pinfunction "VCC_16") (pintype "power_in"))
    )
    (net (code "70") (name "5V_RS485") (class "Default")
      (node (ref "C18") (pin "2") (pinfunction "2_2") (pintype "passive"))
      (node (ref "C20") (pin "2") (pinfunction "2_2") (pintype "passive"))
      (node (ref "C21") (pin "2") (pinfunction "2_2") (pintype "passive"))
      (node (ref "C22") (pin "2") (pinfunction "2_2") (pintype "passive"))
      (node (ref "R22") (pin "2") (pinfunction "2_2") (pintype "passive"))
      (node (ref "R23") (pin "2") (pinfunction "2_2") (pintype "passive"))
      (node (ref "R26") (pin "2") (pinfunction "2_2") (pintype "passive"))
      (node (ref "R27") (pin "2") (pinfunction "2_2") (pintype "passive"))
      (node (ref "R31") (pin "1") (pinfunction "1_1") (pintype "passive"))
      (node (ref "U10") (pin "8") (pinfunction "VCC_8") (pintype "passive"))
      (node (ref "U11") (pin "7") (pinfunction "V0_7") (pintype "passive"))
      (node (ref "U11") (pin "8") (pinfunction "VCC_8") (pintype "passive"))
      (node (ref "U12") (pin "7") (pinfunction "V0_7") (pintype "passive"))
      (node (ref "U12") (pin "8") (pinfunction "VCC_8") (pintype "passive"))
      (node (ref "U9") (pin "4") (pinfunction "Vout_4") (pintype "passive"))
    )
    (net (code "71") (name "24V") (class "Default")
      (node (ref "C1") (pin "1") (pinfunction "1_1") (pintype "passive"))
      (node (ref "D1") (pin "2") (pinfunction "K_2") (pintype "passive"))
      (node (ref "D2") (pin "1") (pinfunction "A_1") (pintype "passive"))
      (node (ref "D5") (pin "1") (pinfunction "A_1") (pintype "passive"))
      (node (ref "U1") (pin "1") (pinfunction "VIN_1") (pintype "power_in"))
    )
    (net (code "72") (name "GND") (class "Default")
      (node (ref "C1") (pin "2") (pinfunction "2_2") (pintype "passive"))
      (node (ref "C17") (pin "2") (pinfunction "2_2") (pintype "passive"))
      (node (ref "C19") (pin "2") (pinfunction "2_2") (pintype "passive"))
      (node (ref "C2") (pin "2") (pinfunction "2_2") (pintype "passive"))
      (node (ref "C23") (pin "2") (pinfunction "2_2") (pintype "passive"))
      (node (ref "C24") (pin "1") (pinfunction "1_1") (pintype "passive"))
      (node (ref "C25") (pin "2") (pinfunction "2_2") (pintype "passive"))
      (node (ref "C26") (pin "1") (pinfunction "1_1") (pintype "passive"))
      (node (ref "C27") (pin "1") (pinfunction "1_1") (pintype "passive"))
      (node (ref "C28") (pin "1") (pinfunction "1_1") (pintype "passive"))
      (node (ref "C29") (pin "2") (pinfunction "2_2") (pintype "passive"))
      (node (ref "C30") (pin "1") (pinfunction "1_1") (pintype "passive"))
      (node (ref "C31") (pin "2") (pinfunction "2_2") (pintype "passive"))
      (node (ref "C32") (pin "2") (pinfunction "2_2") (pintype "passive"))
      (node (ref "C4_") (pin "2") (pinfunction "2_2") (pintype "passive"))
      (node (ref "C6") (pin "2") (pinfunction "2_2") (pintype "passive"))
      (node (ref "C7") (pin "1") (pinfunction "1_1") (pintype "passive"))
      (node (ref "C8") (pin "2") (pinfunction "2_2") (pintype "passive"))
      (node (ref "D5") (pin "2") (pinfunction "K_2") (pintype "passive"))
      (node (ref "D6") (pin "1") (pinfunction "A_1") (pintype "passive"))
      (node (ref "D9") (pin "1") (pinfunction "A_1") (pintype "passive"))
      (node (ref "J1") (pin "2") (pinfunction "2_2") (pintype "passive"))
      (node (ref "J2") (pin "A1_B12") (pinfunction "GND_A1_B12") (pintype "power_in"))
      (node (ref "J2") (pin "B1_A12") (pinfunction "GND_B1_A12") (pintype "power_in"))
      (node (ref "J5") (pin "8") (pinfunction "CHS_GND_8") (pintype "passive"))
      (node (ref "R1") (pin "1") (pinfunction "1_1") (pintype "passive"))
      (node (ref "R10") (pin "2") (pinfunction "2_2") (pintype "passive"))
      (node (ref "R11") (pin "1") (pinfunction "1_1") (pintype "passive"))
      (node (ref "R13") (pin "1") (pinfunction "1_1") (pintype "passive"))
      (node (ref "R2") (pin "1") (pinfunction "1_1") (pintype "passive"))
      (node (ref "R3") (pin "1") (pinfunction "1_1") (pintype "passive"))
      (node (ref "R4") (pin "2") (pinfunction "2_2") (pintype "passive"))
      (node (ref "R5") (pin "2") (pinfunction "2_2") (pintype "passive"))
      (node (ref "SW1") (pin "1") (pinfunction "1_1") (pintype "passive"))
      (node (ref "SW2") (pin "2") (pinfunction "2_2") (pintype "passive"))
      (node (ref "U1") (pin "3") (pinfunction "GND_3") (pintype "power_in"))
      (node (ref "U1") (pin "5") (pinfunction "~{ON}/OFF_5") (pintype "input"))
      (node (ref "U13") (pin "5") (pinfunction "VEE_5") (pintype "passive"))
      (node (ref "U14") (pin "17") (pinfunction "GND_17") (pintype "passive"))
      (node (ref "U15") (pin "1") (pinfunction "GND_1") (pintype "power_in"))
      (node (ref "U15") (pin "40") (pinfunction "GND_40") (pintype "power_in"))
      (node (ref "U15") (pin "41") (pinfunction "GND_41") (pintype "power_in"))
      (node (ref "U15") (pin "42") (pinfunction "GND_42") (pintype "power_in"))
      (node (ref "U15") (pin "43") (pinfunction "GND_43") (pintype "power_in"))
      (node (ref "U15") (pin "44") (pinfunction "GND_44") (pintype "power_in"))
      (node (ref "U15") (pin "45") (pinfunction "GND_45") (pintype "power_in"))
      (node (ref "U15") (pin "46") (pinfunction "GND_46") (pintype "power_in"))
      (node (ref "U15") (pin "47") (pinfunction "GND_47") (pintype "power_in"))
      (node (ref "U15") (pin "48") (pinfunction "GND_48") (pintype "power_in"))
      (node (ref "U15") (pin "49") (pinfunction "GND_49") (pintype "power_in"))
      (node (ref "U16") (pin "11") (pinfunction "E_11") (pintype "passive"))
      (node (ref "U16") (pin "13") (pinfunction "E_13") (pintype "passive"))
      (node (ref "U16") (pin "15") (pinfunction "E_15") (pintype "passive"))
      (node (ref "U16") (pin "9") (pinfunction "E_9") (pintype "passive"))
      (node (ref "U17") (pin "11") (pinfunction "E_11") (pintype "passive"))
      (node (ref "U17") (pin "13") (pinfunction "E_13") (pintype "passive"))
      (node (ref "U17") (pin "15") (pinfunction "E_15") (pintype "passive"))
      (node (ref "U17") (pin "9") (pinfunction "E_9") (pintype "passive"))
      (node (ref "U18") (pin "11") (pinfunction "E_11") (pintype "passive"))
      (node (ref "U18") (pin "9") (pinfunction "E_9") (pintype "passive"))
      (node (ref "U19") (pin "11") (pinfunction "E_11") (pintype "passive"))
      (node (ref "U19") (pin "9") (pinfunction "E_9") (pintype "passive"))
      (node (ref "U2") (pin "2") (pinfunction "GND_2") (pintype "power_in"))
      (node (ref "U3") (pin "5") (pinfunction "GND_5") (pintype "power_in"))
      (node (ref "U4") (pin "3") (pinfunction "CTL_3") (pintype "input"))
      (node (ref "U5") (pin "1") (pinfunction "GND_1") (pintype "passive"))
      (node (ref "U8") (pin "5") (pinfunction "VEE_5") (pintype "passive"))
      (node (ref "U9") (pin "1") (pinfunction "GND_1") (pintype "passive"))
    )
    (net (code "73") (name "GND_RS232") (class "Default")
      (node (ref "C10") (pin "1") (pinfunction "1_1") (pintype "passive"))
      (node (ref "C11") (pin "2") (pinfunction "2_2") (pintype "passive"))
      (node (ref "C14") (pin "1") (pinfunction "1_1") (pintype "passive"))
      (node (ref "C16") (pin "1") (pinfunction "1_1") (pintype "passive"))
      (node (ref "C21") (pin "1") (pinfunction "1_1") (pintype "passive"))
      (node (ref "C22") (pin "1") (pinfunction "1_1") (pintype "passive"))
      (node (ref "C9") (pin "1") (pinfunction "1_1") (pintype "passive"))
      (node (ref "D12") (pin "2") (pinfunction "K_2") (pintype "passive"))
      (node (ref "D13") (pin "2") (pinfunction "K_2") (pintype "passive"))
      (node (ref "J3") (pin "5") (pinfunction "5_5") (pintype "passive"))
      (node (ref "U5") (pin "3") (pinfunction "0V_3") (pintype "passive"))
      (node (ref "U6") (pin "5") (pinfunction "VEE_5") (pintype "passive"))
      (node (ref "U7") (pin "15") (pinfunction "GND_15") (pintype "power_in"))
    )
    (net (code "74") (name "GND_RS485") (class "Default")
      (node (ref "C18") (pin "1") (pinfunction "1_1") (pintype "passive"))
      (node (ref "C20") (pin "1") (pinfunction "1_1") (pintype "passive"))
      (node (ref "D16") (pin "1") (pinfunction "A_1") (pintype "passive"))
      (node (ref "D18") (pin "2") (pinfunction "K_2") (pintype "passive"))
      (node (ref "J4") (pin "3") (pinfunction "3_3") (pintype "passive"))
      (node (ref "U10") (pin "5") (pinfunction "GND_5") (pintype "passive"))
      (node (ref "U11") (pin "5") (pinfunction "VEE_5") (pintype "passive"))
      (node (ref "U12") (pin "5") (pinfunction "VEE_5") (pintype "passive"))
      (node (ref "U9") (pin "3") (pinfunction "0V_3") (pintype "passive"))
    )
    (net (code "75") (name "ICOM") (class "Default")
      (node (ref "D23") (pin "1") (pinfunction "A_1") (pintype "passive"))
      (node (ref "D24") (pin "1") (pinfunction "A_1") (pintype "passive"))
      (node (ref "D25") (pin "1") (pinfunction "A_1") (pintype "passive"))
      (node (ref "D26") (pin "1") (pinfunction "A_1") (pintype "passive"))
      (node (ref "D29") (pin "1") (pinfunction "A_1") (pintype "passive"))
      (node (ref "D30") (pin "1") (pinfunction "A_1") (pintype "passive"))
      (node (ref "D33") (pin "1") (pinfunction "A_1") (pintype "passive"))
      (node (ref "D34") (pin "1") (pinfunction "A_1") (pintype "passive"))
      (node (ref "D37") (pin "1") (pinfunction "A_1") (pintype "passive"))
      (node (ref "D38") (pin "1") (pinfunction "A_1") (pintype "passive"))
      (node (ref "D39") (pin "1") (pinfunction "A_1") (pintype "passive"))
      (node (ref "D40") (pin "1") (pinfunction "A_1") (pintype "passive"))
      (node (ref "JP6") (pin "1") (pinfunction "1_1") (pintype "passive"))
      (node (ref "RN1-1") (pin "2") (pinfunction "2_2") (pintype "passive"))
      (node (ref "RN1-2") (pin "2") (pinfunction "2_2") (pintype "passive"))
      (node (ref "RN1-3") (pin "2") (pinfunction "2_2") (pintype "passive"))
      (node (ref "RN1-4") (pin "2") (pinfunction "2_2") (pintype "passive"))
      (node (ref "RN1-5") (pin "2") (pinfunction "2_2") (pintype "passive"))
      (node (ref "RN1-6") (pin "2") (pinfunction "2_2") (pintype "passive"))
      (node (ref "RN2-1") (pin "2") (pinfunction "2_2") (pintype "passive"))
      (node (ref "RN2-2") (pin "2") (pinfunction "2_2") (pintype "passive"))
      (node (ref "RN2-3") (pin "2") (pinfunction "2_2") (pintype "passive"))
      (node (ref "RN2-4") (pin "2") (pinfunction "2_2") (pintype "passive"))
      (node (ref "RN2-5") (pin "2") (pinfunction "2_2") (pintype "passive"))
      (node (ref "RN2-6") (pin "2") (pinfunction "2_2") (pintype "passive"))
    )
    (net (code "76") (name "Net-(C5-Pad2)") (class "Default")
      (node (ref "C5") (pin "2") (pinfunction "2_2") (pintype "passive"))
      (node (ref "R11") (pin "2") (pinfunction "2_2") (pintype "passive"))
    )
    (net (code "77") (name "Net-(C7-Pad2)") (class "Default")
      (node (ref "C7") (pin "2") (pinfunction "2_2") (pintype "passive"))
      (node (ref "J2") (pin "SH1") (pinfunction "SHIELD_SH1") (pintype "passive"))
      (node (ref "J2") (pin "SH2") (pinfunction "SHIELD_SH2") (pintype "passive"))
      (node (ref "J2") (pin "SH3") (pinfunction "SHIELD_SH3") (pintype "passive"))
      (node (ref "J2") (pin "SH4") (pinfunction "SHIELD_SH4") (pintype "passive"))
    )
    (net (code "78") (name "Net-(C26-Pad2)") (class "Default")
      (node (ref "C26") (pin "2") (pinfunction "2_2") (pintype "passive"))
      (node (ref "R32") (pin "2") (pinfunction "2_2") (pintype "passive"))
    )
    (net (code "79") (name "Net-(C30-Pad2)") (class "Default")
      (node (ref "C30") (pin "2") (pinfunction "2_2") (pintype "passive"))
      (node (ref "J5") (pin "13") (pinfunction "SHIELD_13") (pintype "passive"))
      (node (ref "J5") (pin "14") (pinfunction "SHIELD_14") (pintype "passive"))
    )
    (net (code "80") (name "Net-(D1-A)") (class "Default")
      (node (ref "D1") (pin "1") (pinfunction "A_1") (pintype "passive"))
      (node (ref "F1") (pin "2") (pinfunction "2_2") (pintype "passive"))
    )
    (net (code "81") (name "Net-(D2-K)") (class "Default")
      (node (ref "D2") (pin "2") (pinfunction "K_2") (pintype "passive"))
      (node (ref "R1") (pin "2") (pinfunction "2_2") (pintype "passive"))
    )
    (net (code "82") (name "Net-(D3-K)") (class "Default")
      (node (ref "D3") (pin "2") (pinfunction "K_2") (pintype "passive"))
      (node (ref "R2") (pin "2") (pinfunction "2_2") (pintype "passive"))
    )
    (net (code "83") (name "Net-(D4-K)") (class "Default")
      (node (ref "D4") (pin "2") (pinfunction "K_2") (pintype "passive"))
      (node (ref "R3") (pin "2") (pinfunction "2_2") (pintype "passive"))
    )
    (net (code "84") (name "Net-(D6-K)") (class "Default")
      (node (ref "D6") (pin "2") (pinfunction "K_2") (pintype "passive"))
      (node (ref "L1") (pin "1") (pinfunction "1_1") (pintype "passive"))
      (node (ref "U1") (pin "2") (pinfunction "OUT_2") (pintype "power_in"))
    )
    (net (code "85") (name "Net-(D8-K)") (class "Default")
      (node (ref "D8") (pin "2") (pinfunction "K_2") (pintype "passive"))
      (node (ref "R7") (pin "2") (pinfunction "2_2") (pintype "passive"))
    )
    (net (code "86") (name "Net-(D9-K)") (class "Default")
      (node (ref "C3") (pin "2") (pinfunction "2_2") (pintype "passive"))
      (node (ref "D9") (pin "2") (pinfunction "K_2") (pintype "passive"))
      (node (ref "L2") (pin "1") (pinfunction "1_1") (pintype "passive"))
      (node (ref "U3") (pin "1") (pinfunction "SW_1") (pintype "output"))
    )
    (net (code "87") (name "Net-(D10-A)") (class "Default")
      (node (ref "D10") (pin "1") (pinfunction "A_1") (pintype "passive"))
      (node (ref "R14") (pin "1") (pinfunction "1_1") (pintype "passive"))
    )
    (net (code "88") (name "Net-(D11-A)") (class "Default")
      (node (ref "D11") (pin "1") (pinfunction "A_1") (pintype "passive"))
      (node (ref "R15") (pin "1") (pinfunction "1_1") (pintype "passive"))
    )
    (net (code "89") (name "Net-(D12-A)") (class "Default")
      (node (ref "D12") (pin "1") (pinfunction "A_1") (pintype "passive"))
      (node (ref "J3") (pin "2") (pinfunction "2_2") (pintype "passive"))
      (node (ref "R18") (pin "1") (pinfunction "1_1") (pintype "passive"))
    )
    (net (code "90") (name "Net-(D13-A)") (class "Default")
      (node (ref "D13") (pin "1") (pinfunction "A_1") (pintype "passive"))
      (node (ref "J3") (pin "3") (pinfunction "3_3") (pintype "passive"))
      (node (ref "R19") (pin "1") (pinfunction "1_1") (pintype "passive"))
    )
    (net (code "91") (name "Net-(D14-A)") (class "Default")
      (node (ref "D14") (pin "1") (pinfunction "A_1") (pintype "passive"))
      (node (ref "R22") (pin "1") (pinfunction "1_1") (pintype "passive"))
    )
    (net (code "92") (name "Net-(D15-A)") (class "Default")
      (node (ref "D15") (pin "1") (pinfunction "A_1") (pintype "passive"))
      (node (ref "R23") (pin "1") (pinfunction "1_1") (pintype "passive"))
    )
    (net (code "93") (name "Net-(D16-K)") (class "Default")
      (node (ref "D16") (pin "2") (pinfunction "K_2") (pintype "passive"))
      (node (ref "D17") (pin "1") (pinfunction "A_1") (pintype "passive"))
      (node (ref "J4") (pin "1") (pinfunction "1_1") (pintype "passive"))
      (node (ref "R24") (pin "1") (pinfunction "1_1") (pintype "passive"))
    )
    (net (code "94") (name "Net-(D17-K)") (class "Default")
      (node (ref "D17") (pin "2") (pinfunction "K_2") (pintype "passive"))
      (node (ref "D18") (pin "1") (pinfunction "A_1") (pintype "passive"))
      (node (ref "J4") (pin "2") (pinfunction "2_2") (pintype "passive"))
      (node (ref "R25") (pin "1") (pinfunction "1_1") (pintype "passive"))
    )
    (net (code "95") (name "Net-(D19-K)") (class "Default")
      (node (ref "D19") (pin "2") (pinfunction "K_2") (pintype "passive"))
      (node (ref "R38") (pin "1") (pinfunction "1_1") (pintype "passive"))
    )
    (net (code "96") (name "Net-(D20-K)") (class "Default")
      (node (ref "D20") (pin "2") (pinfunction "K_2") (pintype "passive"))
      (node (ref "R39") (pin "1") (pinfunction "1_1") (pintype "passive"))
    )
    (net (code "97") (name "Net-(D21-K)") (class "Default")
      (node (ref "D21") (pin "2") (pinfunction "K_2") (pintype "passive"))
      (node (ref "R40") (pin "1") (pinfunction "1_1") (pintype "passive"))
    )
    (net (code "98") (name "Net-(D22-K)") (class "Default")
      (node (ref "D22") (pin "2") (pinfunction "K_2") (pintype "passive"))
      (node (ref "R41") (pin "1") (pinfunction "1_1") (pintype "passive"))
    )
    (net (code "99") (name "Net-(D27-K)") (class "Default")
      (node (ref "D27") (pin "2") (pinfunction "K_2") (pintype "passive"))
      (node (ref "R42") (pin "1") (pinfunction "1_1") (pintype "passive"))
    )
    (net (code "100") (name "Net-(D28-K)") (class "Default")
      (node (ref "D28") (pin "2") (pinfunction "K_2") (pintype "passive"))
      (node (ref "R43") (pin "1") (pinfunction "1_1") (pintype "passive"))
    )
    (net (code "101") (name "Net-(D31-K)") (class "Default")
      (node (ref "D31") (pin "2") (pinfunction "K_2") (pintype "passive"))
      (node (ref "R46") (pin "1") (pinfunction "1_1") (pintype "passive"))
    )
    (net (code "102") (name "Net-(D32-K)") (class "Default")
      (node (ref "D32") (pin "2") (pinfunction "K_2") (pintype "passive"))
      (node (ref "R45") (pin "1") (pinfunction "1_1") (pintype "passive"))
    )
    (net (code "103") (name "Net-(D35-K)") (class "Default")
      (node (ref "D35") (pin "2") (pinfunction "K_2") (pintype "passive"))
      (node (ref "R44") (pin "1") (pinfunction "1_1") (pintype "passive"))
    )
    (net (code "104") (name "Net-(D36-K)") (class "Default")
      (node (ref "D36") (pin "2") (pinfunction "K_2") (pintype "passive"))
      (node (ref "R47") (pin "1") (pinfunction "1_1") (pintype "passive"))
    )
    (net (code "105") (name "Net-(D41-K)") (class "Default")
      (node (ref "D41") (pin "2") (pinfunction "K_2") (pintype "passive"))
      (node (ref "R48") (pin "1") (pinfunction "1_1") (pintype "passive"))
    )
    (net (code "106") (name "Net-(D42-K)") (class "Default")
      (node (ref "D42") (pin "2") (pinfunction "K_2") (pintype "passive"))
      (node (ref "R49") (pin "1") (pinfunction "1_1") (pintype "passive"))
    )
    (net (code "107") (name "Net-(D43-K)") (class "Default")
      (node (ref "D43") (pin "2") (pinfunction "K_2") (pintype "passive"))
      (node (ref "R50") (pin "1") (pinfunction "1_1") (pintype "passive"))
    )
    (net (code "108") (name "Net-(D44-K)") (class "Default")
      (node (ref "D44") (pin "2") (pinfunction "K_2") (pintype "passive"))
      (node (ref "R51") (pin "1") (pinfunction "1_1") (pintype "passive"))
    )
    (net (code "109") (name "Net-(D45-A)") (class "Default")
      (node (ref "D45") (pin "1") (pinfunction "A_1") (pintype "passive"))
      (node (ref "RN5-4") (pin "1") (pinfunction "1_1") (pintype "passive"))
    )
    (net (code "110") (name "Net-(D46-A)") (class "Default")
      (node (ref "D46") (pin "1") (pinfunction "A_1") (pintype "passive"))
      (node (ref "RN5-3") (pin "1") (pinfunction "1_1") (pintype "passive"))
    )
    (net (code "111") (name "Net-(D47-A)") (class "Default")
      (node (ref "D47") (pin "1") (pinfunction "A_1") (pintype "passive"))
      (node (ref "RN5-2") (pin "1") (pinfunction "1_1") (pintype "passive"))
    )
    (net (code "112") (name "Net-(D50-A)") (class "Default")
      (node (ref "D50") (pin "1") (pinfunction "A_1") (pintype "passive"))
      (node (ref "RN5-1") (pin "1") (pinfunction "1_1") (pintype "passive"))
    )
    (net (code "113") (name "Net-(D54-A)") (class "Default")
      (node (ref "D54") (pin "1") (pinfunction "A_1") (pintype "passive"))
      (node (ref "RN8-4") (pin "1") (pinfunction "1_1") (pintype "passive"))
    )
    (net (code "114") (name "Net-(D56-A)") (class "Default")
      (node (ref "D56") (pin "1") (pinfunction "A_1") (pintype "passive"))
      (node (ref "RN8-3") (pin "1") (pinfunction "1_1") (pintype "passive"))
    )
    (net (code "115") (name "Net-(D58-A)") (class "Default")
      (node (ref "D58") (pin "1") (pinfunction "A_1") (pintype "passive"))
      (node (ref "RN8-2") (pin "1") (pinfunction "1_1") (pintype "passive"))
    )
    (net (code "116") (name "Net-(D61-A)") (class "Default")
      (node (ref "D61") (pin "1") (pinfunction "A_1") (pintype "passive"))
      (node (ref "RN8-1") (pin "1") (pinfunction "1_1") (pintype "passive"))
    )
    (net (code "117") (name "Net-(F1-Pad1)") (class "Default")
      (node (ref "F1") (pin "1") (pinfunction "1_1") (pintype "passive"))
      (node (ref "J1") (pin "1") (pinfunction "1_1") (pintype "passive"))
    )
    (net (code "118") (name "Net-(J2-CC1)") (class "Default")
      (node (ref "J2") (pin "A5") (pinfunction "CC1_A5") (pintype "passive"))
      (node (ref "R5") (pin "1") (pinfunction "1_1") (pintype "passive"))
    )
    (net (code "119") (name "Net-(J2-CC2)") (class "Default")
      (node (ref "J2") (pin "B5") (pinfunction "CC2_B5") (pintype "passive"))
      (node (ref "R4") (pin "1") (pinfunction "1_1") (pintype "passive"))
    )
    (net (code "120") (name "Net-(J3-MH1)") (class "Default")
      (node (ref "C11") (pin "1") (pinfunction "1_1") (pintype "passive"))
      (node (ref "J3") (pin "10") (pinfunction "MH1_10") (pintype "passive"))
      (node (ref "J3") (pin "11") (pinfunction "MH2_11") (pintype "passive"))
    )
    (net (code "121") (name "Net-(J5-LED.G_A)") (class "Default")
      (node (ref "J5") (pin "9") (pinfunction "LED.G_A_9") (pintype "passive"))
      (node (ref "R35") (pin "1") (pinfunction "1_1") (pintype "passive"))
    )
    (net (code "122") (name "Net-(J5-LED.Y_A)") (class "Default")
      (node (ref "J5") (pin "12") (pinfunction "LED.Y_A_12") (pintype "passive"))
      (node (ref "R34") (pin "1") (pinfunction "1_1") (pintype "passive"))
    )
    (net (code "123") (name "Net-(J5-RCT)") (class "Default")
      (node (ref "C28") (pin "2") (pinfunction "2_2") (pintype "passive"))
      (node (ref "J5") (pin "5") (pinfunction "RCT_5") (pintype "passive"))
    )
    (net (code "124") (name "Net-(J5-TCT)") (class "Default")
      (node (ref "C27") (pin "2") (pinfunction "2_2") (pintype "passive"))
      (node (ref "J5") (pin "4") (pinfunction "TCT_4") (pintype "passive"))
    )
    (net (code "125") (name "Net-(Q1-G)") (class "Default")
      (node (ref "Q1") (pin "1") (pinfunction "G_1") (pintype "passive"))
      (node (ref "U4") (pin "5") (pinfunction "GATE_5") (pintype "passive"))
    )
    (net (code "126") (name "Net-(Q2-B)") (class "Default")
      (node (ref "Q2") (pin "1") (pinfunction "B_1") (pintype "passive"))
      (node (ref "R52") (pin "2") (pinfunction "2_2") (pintype "passive"))
      (node (ref "R54") (pin "2") (pinfunction "2_2") (pintype "passive"))
    )
    (net (code "127") (name "Net-(Q3-B)") (class "Default")
      (node (ref "Q3") (pin "1") (pinfunction "B_1") (pintype "passive"))
      (node (ref "R53") (pin "2") (pinfunction "2_2") (pintype "passive"))
      (node (ref "R55") (pin "2") (pinfunction "2_2") (pintype "passive"))
    )
    (net (code "128") (name "Net-(Q4-B)") (class "Default")
      (node (ref "Q4") (pin "1") (pinfunction "B_1") (pintype "passive"))
      (node (ref "R56") (pin "2") (pinfunction "2_2") (pintype "passive"))
      (node (ref "R58") (pin "2") (pinfunction "2_2") (pintype "passive"))
    )
    (net (code "129") (name "Net-(Q5-B)") (class "Default")
      (node (ref "Q5") (pin "1") (pinfunction "B_1") (pintype "passive"))
      (node (ref "R57") (pin "2") (pinfunction "2_2") (pintype "passive"))
      (node (ref "R59") (pin "2") (pinfunction "2_2") (pintype "passive"))
    )
    (net (code "130") (name "Net-(Q6-B)") (class "Default")
      (node (ref "Q6") (pin "1") (pinfunction "B_1") (pintype "passive"))
      (node (ref "R60") (pin "2") (pinfunction "2_2") (pintype "passive"))
      (node (ref "R62") (pin "2") (pinfunction "2_2") (pintype "passive"))
    )
    (net (code "131") (name "Net-(Q7-B)") (class "Default")
      (node (ref "Q7") (pin "1") (pinfunction "B_1") (pintype "passive"))
      (node (ref "R61") (pin "2") (pinfunction "2_2") (pintype "passive"))
      (node (ref "R63") (pin "2") (pinfunction "2_2") (pintype "passive"))
    )
    (net (code "132") (name "Net-(Q8-B)") (class "Default")
      (node (ref "Q8") (pin "1") (pinfunction "B_1") (pintype "passive"))
      (node (ref "R64") (pin "2") (pinfunction "2_2") (pintype "passive"))
      (node (ref "R66") (pin "2") (pinfunction "2_2") (pintype "passive"))
    )
    (net (code "133") (name "Net-(Q9-B)") (class "Default")
      (node (ref "Q9") (pin "1") (pinfunction "B_1") (pintype "passive"))
      (node (ref "R65") (pin "2") (pinfunction "2_2") (pintype "passive"))
      (node (ref "R67") (pin "2") (pinfunction "2_2") (pintype "passive"))
    )
    (net (code "134") (name "Net-(R52-Pad1)") (class "Default")
      (node (ref "R52") (pin "1") (pinfunction "1_1") (pintype "passive"))
      (node (ref "U20") (pin "15") (pinfunction "E_15") (pintype "passive"))
    )
    (net (code "135") (name "Net-(R53-Pad1)") (class "Default")
      (node (ref "R53") (pin "1") (pinfunction "1_1") (pintype "passive"))
      (node (ref "U21") (pin "15") (pinfunction "E_15") (pintype "passive"))
    )
    (net (code "136") (name "Net-(R56-Pad1)") (class "Default")
      (node (ref "R56") (pin "1") (pinfunction "1_1") (pintype "passive"))
      (node (ref "U20") (pin "13") (pinfunction "E_13") (pintype "passive"))
    )
    (net (code "137") (name "Net-(R57-Pad1)") (class "Default")
      (node (ref "R57") (pin "1") (pinfunction "1_1") (pintype "passive"))
      (node (ref "U21") (pin "13") (pinfunction "E_13") (pintype "passive"))
    )
    (net (code "138") (name "Net-(R60-Pad1)") (class "Default")
      (node (ref "R60") (pin "1") (pinfunction "1_1") (pintype "passive"))
      (node (ref "U20") (pin "11") (pinfunction "E_11") (pintype "passive"))
    )
    (net (code "139") (name "Net-(R61-Pad1)") (class "Default")
      (node (ref "R61") (pin "1") (pinfunction "1_1") (pintype "passive"))
      (node (ref "U21") (pin "11") (pinfunction "E_11") (pintype "passive"))
    )
    (net (code "140") (name "Net-(R64-Pad1)") (class "Default")
      (node (ref "R64") (pin "1") (pinfunction "1_1") (pintype "passive"))
      (node (ref "U20") (pin "9") (pinfunction "E_9") (pintype "passive"))
    )
    (net (code "141") (name "Net-(R65-Pad1)") (class "Default")
      (node (ref "R65") (pin "1") (pinfunction "1_1") (pintype "passive"))
      (node (ref "U21") (pin "9") (pinfunction "E_9") (pintype "passive"))
    )
    (net (code "142") (name "Net-(RN1-1-Pad1)") (class "Default")
      (node (ref "RN1-1") (pin "1") (pinfunction "1_1") (pintype "passive"))
      (node (ref "RN3-1") (pin "2") (pinfunction "2_2") (pintype "passive"))
      (node (ref "U16") (pin "1") (pinfunction "+_1") (pintype "passive"))
    )
    (net (code "143") (name "Net-(RN1-2-Pad1)") (class "Default")
      (node (ref "RN1-2") (pin "1") (pinfunction "1_1") (pintype "passive"))
      (node (ref "RN3-2") (pin "2") (pinfunction "2_2") (pintype "passive"))
      (node (ref "U16") (pin "3") (pinfunction "+_3") (pintype "passive"))
    )
    (net (code "144") (name "Net-(RN1-3-Pad1)") (class "Default")
      (node (ref "RN1-3") (pin "1") (pinfunction "1_1") (pintype "passive"))
      (node (ref "RN3-3") (pin "2") (pinfunction "2_2") (pintype "passive"))
      (node (ref "U16") (pin "5") (pinfunction "+_5") (pintype "passive"))
    )
    (net (code "145") (name "Net-(RN1-4-Pad1)") (class "Default")
      (node (ref "RN1-4") (pin "1") (pinfunction "1_1") (pintype "passive"))
      (node (ref "RN3-4") (pin "2") (pinfunction "2_2") (pintype "passive"))
      (node (ref "U16") (pin "7") (pinfunction "+_7") (pintype "passive"))
    )
    (net (code "146") (name "Net-(RN1-5-Pad1)") (class "Default")
      (node (ref "RN1-5") (pin "1") (pinfunction "1_1") (pintype "passive"))
      (node (ref "RN3-5") (pin "2") (pinfunction "2_2") (pintype "passive"))
      (node (ref "U18") (pin "5") (pinfunction "+_5") (pintype "passive"))
    )
    (net (code "147") (name "Net-(RN1-6-Pad1)") (class "Default")
      (node (ref "RN1-6") (pin "1") (pinfunction "1_1") (pintype "passive"))
      (node (ref "RN3-6") (pin "2") (pinfunction "2_2") (pintype "passive"))
      (node (ref "U18") (pin "7") (pinfunction "+_7") (pintype "passive"))
    )
    (net (code "148") (name "Net-(RN2-1-Pad1)") (class "Default")
      (node (ref "RN2-1") (pin "1") (pinfunction "1_1") (pintype "passive"))
      (node (ref "RN4-1") (pin "2") (pinfunction "2_2") (pintype "passive"))
      (node (ref "U17") (pin "1") (pinfunction "+_1") (pintype "passive"))
    )
    (net (code "149") (name "Net-(RN2-2-Pad1)") (class "Default")
      (node (ref "RN2-2") (pin "1") (pinfunction "1_1") (pintype "passive"))
      (node (ref "RN4-2") (pin "2") (pinfunction "2_2") (pintype "passive"))
      (node (ref "U17") (pin "3") (pinfunction "+_3") (pintype "passive"))
    )
    (net (code "150") (name "Net-(RN2-3-Pad1)") (class "Default")
      (node (ref "RN2-3") (pin "1") (pinfunction "1_1") (pintype "passive"))
      (node (ref "RN4-3") (pin "2") (pinfunction "2_2") (pintype "passive"))
      (node (ref "U17") (pin "5") (pinfunction "+_5") (pintype "passive"))
    )
    (net (code "151") (name "Net-(RN2-4-Pad1)") (class "Default")
      (node (ref "RN2-4") (pin "1") (pinfunction "1_1") (pintype "passive"))
      (node (ref "RN4-4") (pin "2") (pinfunction "2_2") (pintype "passive"))
      (node (ref "U17") (pin "7") (pinfunction "+_7") (pintype "passive"))
    )
    (net (code "152") (name "Net-(RN2-5-Pad1)") (class "Default")
      (node (ref "RN2-5") (pin "1") (pinfunction "1_1") (pintype "passive"))
      (node (ref "RN4-5") (pin "2") (pinfunction "2_2") (pintype "passive"))
      (node (ref "U19") (pin "5") (pinfunction "+_5") (pintype "passive"))
    )
    (net (code "153") (name "Net-(RN2-6-Pad1)") (class "Default")
      (node (ref "RN2-6") (pin "1") (pinfunction "1_1") (pintype "passive"))
      (node (ref "RN4-6") (pin "2") (pinfunction "2_2") (pintype "passive"))
      (node (ref "U19") (pin "7") (pinfunction "+_7") (pintype "passive"))
    )
    (net (code "154") (name "Net-(RN6-1-Pad1)") (class "Default")
      (node (ref "RN6-1") (pin "1") (pinfunction "1_1") (pintype "passive"))
      (node (ref "U20") (pin "1") (pinfunction "+_1") (pintype "passive"))
    )
    (net (code "155") (name "Net-(RN6-2-Pad1)") (class "Default")
      (node (ref "RN6-2") (pin "1") (pinfunction "1_1") (pintype "passive"))
      (node (ref "U20") (pin "3") (pinfunction "+_3") (pintype "passive"))
    )
    (net (code "156") (name "Net-(RN6-3-Pad1)") (class "Default")
      (node (ref "RN6-3") (pin "1") (pinfunction "1_1") (pintype "passive"))
      (node (ref "U20") (pin "5") (pinfunction "+_5") (pintype "passive"))
    )
    (net (code "157") (name "Net-(RN6-4-Pad1)") (class "Default")
      (node (ref "RN6-4") (pin "1") (pinfunction "1_1") (pintype "passive"))
      (node (ref "U20") (pin "7") (pinfunction "+_7") (pintype "passive"))
    )
    (net (code "158") (name "Net-(RN7-1-Pad1)") (class "Default")
      (node (ref "RN7-1") (pin "1") (pinfunction "1_1") (pintype "passive"))
      (node (ref "U21") (pin "1") (pinfunction "+_1") (pintype "passive"))
    )
    (net (code "159") (name "Net-(RN7-2-Pad1)") (class "Default")
      (node (ref "RN7-2") (pin "1") (pinfunction "1_1") (pintype "passive"))
      (node (ref "U21") (pin "3") (pinfunction "+_3") (pintype "passive"))
    )
    (net (code "160") (name "Net-(RN7-3-Pad1)") (class "Default")
      (node (ref "RN7-3") (pin "1") (pinfunction "1_1") (pintype "passive"))
      (node (ref "U21") (pin "5") (pinfunction "+_5") (pintype "passive"))
    )
    (net (code "161") (name "Net-(RN7-4-Pad1)") (class "Default")
      (node (ref "RN7-4") (pin "1") (pinfunction "1_1") (pintype "passive"))
      (node (ref "U21") (pin "7") (pinfunction "+_7") (pintype "passive"))
    )
    (net (code "162") (name "Net-(U3-BST)") (class "Default")
      (node (ref "C3") (pin "1") (pinfunction "1_1") (pintype "passive"))
      (node (ref "U3") (pin "8") (pinfunction "BST_8") (pintype "passive"))
    )
    (net (code "163") (name "Net-(U3-COMP)") (class "Default")
      (node (ref "C5") (pin "1") (pinfunction "1_1") (pintype "passive"))
      (node (ref "U3") (pin "3") (pinfunction "COMP_3") (pintype "output"))
    )
    (net (code "164") (name "Net-(U3-EN)") (class "Default")
      (node (ref "R6") (pin "1") (pinfunction "1_1") (pintype "passive"))
      (node (ref "U3") (pin "2") (pinfunction "EN_2") (pintype "input"))
    )
    (net (code "165") (name "Net-(U3-FB)") (class "Default")
      (node (ref "R12") (pin "1") (pinfunction "1_1") (pintype "passive"))
      (node (ref "R13") (pin "2") (pinfunction "2_2") (pintype "passive"))
      (node (ref "U3") (pin "4") (pinfunction "FB_4") (pintype "input"))
    )
    (net (code "166") (name "Net-(U3-FREQ)") (class "Default")
      (node (ref "R10") (pin "1") (pinfunction "1_1") (pintype "passive"))
      (node (ref "U3") (pin "6") (pinfunction "FREQ_6") (pintype "input"))
    )
    (net (code "167") (name "Net-(U4-STAT)") (class "Default")
      (node (ref "R7") (pin "1") (pinfunction "1_1") (pintype "passive"))
      (node (ref "U4") (pin "4") (pinfunction "STAT_4") (pintype "output"))
    )
    (net (code "168") (name "Net-(U6-ANODE)") (class "Default")
      (node (ref "R17") (pin "1") (pinfunction "1_1") (pintype "passive"))
      (node (ref "U6") (pin "2") (pinfunction "ANODE_2") (pintype "passive"))
    )
    (net (code "169") (name "Net-(U7-C+)") (class "Default")
      (node (ref "C12") (pin "2") (pinfunction "2_2") (pintype "passive"))
      (node (ref "U7") (pin "1") (pinfunction "C+_1") (pintype "passive"))
    )
    (net (code "170") (name "Net-(U7-C1-)") (class "Default")
      (node (ref "C12") (pin "1") (pinfunction "1_1") (pintype "passive"))
      (node (ref "U7") (pin "3") (pinfunction "C1-_3") (pintype "passive"))
    )
    (net (code "171") (name "Net-(U7-C2+)") (class "Default")
      (node (ref "C13") (pin "1") (pinfunction "1_1") (pintype "passive"))
      (node (ref "U7") (pin "4") (pinfunction "C2+_4") (pintype "passive"))
    )
    (net (code "172") (name "Net-(U7-C2-)") (class "Default")
      (node (ref "C13") (pin "2") (pinfunction "2_2") (pintype "passive"))
      (node (ref "U7") (pin "5") (pinfunction "C2-_5") (pintype "passive"))
    )
    (net (code "173") (name "Net-(U7-R1IN)") (class "Default")
      (node (ref "R19") (pin "2") (pinfunction "2_2") (pintype "passive"))
      (node (ref "U7") (pin "13") (pinfunction "R1IN_13") (pintype "input"))
    )
    (net (code "174") (name "Net-(U7-T1OUT)") (class "Default")
      (node (ref "R18") (pin "2") (pinfunction "2_2") (pintype "passive"))
      (node (ref "U7") (pin "14") (pinfunction "T1OUT_14") (pintype "output"))
    )
    (net (code "175") (name "Net-(U7-V+)") (class "Default")
      (node (ref "C15") (pin "1") (pinfunction "1_1") (pintype "passive"))
      (node (ref "U7") (pin "2") (pinfunction "V+_2") (pintype "passive"))
    )
    (net (code "176") (name "Net-(U7-V-)") (class "Default")
      (node (ref "C16") (pin "2") (pinfunction "2_2") (pintype "passive"))
      (node (ref "U7") (pin "6") (pinfunction "V-_6") (pintype "passive"))
    )
    (net (code "177") (name "Net-(U8-ANODE)") (class "Default")
      (node (ref "R21") (pin "2") (pinfunction "2_2") (pintype "passive"))
      (node (ref "U8") (pin "2") (pinfunction "ANODE_2") (pintype "passive"))
    )
    (net (code "178") (name "Net-(U10-A)") (class "Default")
      (node (ref "R25") (pin "2") (pinfunction "2_2") (pintype "passive"))
      (node (ref "U10") (pin "6") (pinfunction "A_6") (pintype "passive"))
    )
    (net (code "179") (name "Net-(U10-B)") (class "Default")
      (node (ref "R24") (pin "2") (pinfunction "2_2") (pintype "passive"))
      (node (ref "U10") (pin "7") (pinfunction "B_7") (pintype "passive"))
    )
    (net (code "180") (name "Net-(U11-ANODE)") (class "Default")
      (node (ref "R29") (pin "1") (pinfunction "1_1") (pintype "passive"))
      (node (ref "U11") (pin "2") (pinfunction "ANODE_2") (pintype "passive"))
    )
    (net (code "181") (name "Net-(U12-ANODE)") (class "Default")
      (node (ref "R30") (pin "1") (pinfunction "1_1") (pintype "passive"))
      (node (ref "U12") (pin "2") (pinfunction "ANODE_2") (pintype "passive"))
    )
    (net (code "182") (name "Net-(U13-ANODE)") (class "Default")
      (node (ref "R31") (pin "2") (pinfunction "2_2") (pintype "passive"))
      (node (ref "U13") (pin "2") (pinfunction "ANODE_2") (pintype "passive"))
    )
    (net (code "183") (name "Net-(U15-EN)") (class "Default")
      (node (ref "R37") (pin "1") (pinfunction "1_1") (pintype "passive"))
      (node (ref "SW2") (pin "1") (pinfunction "1_1") (pintype "passive"))
      (node (ref "U15") (pin "3") (pinfunction "EN_3") (pintype "input"))
    )
    (net (code "184") (name "Net-(U15-IO0)") (class "Default")
      (node (ref "R36") (pin "1") (pinfunction "1_1") (pintype "passive"))
      (node (ref "SW1") (pin "2") (pinfunction "2_2") (pintype "passive"))
      (node (ref "U15") (pin "27") (pinfunction "IO0_27") (pintype "bidirectional"))
    )
    (net (code "185") (name "Net-(U15-IO1)") (class "Default")
      (node (ref "R39") (pin "2") (pinfunction "2_2") (pintype "passive"))
      (node (ref "U15") (pin "39") (pinfunction "IO1_39") (pintype "bidirectional"))
    )
    (net (code "186") (name "Net-(U15-IO4)") (class "Default")
      (node (ref "R38") (pin "2") (pinfunction "2_2") (pintype "passive"))
      (node (ref "U15") (pin "4") (pinfunction "IO4_4") (pintype "bidirectional"))
    )
    (net (code "187") (name "OCOM_N") (class "Default")
      (node (ref "D48") (pin "2") (pinfunction "K_2") (pintype "passive"))
      (node (ref "D49") (pin "2") (pinfunction "K_2") (pintype "passive"))
      (node (ref "D51") (pin "2") (pinfunction "K_2") (pintype "passive"))
      (node (ref "D52") (pin "2") (pinfunction "K_2") (pintype "passive"))
      (node (ref "D53") (pin "2") (pinfunction "K_2") (pintype "passive"))
      (node (ref "D55") (pin "2") (pinfunction "K_2") (pintype "passive"))
      (node (ref "D57") (pin "2") (pinfunction "K_2") (pintype "passive"))
      (node (ref "D59") (pin "2") (pinfunction "K_2") (pintype "passive"))
      (node (ref "D60") (pin "2") (pinfunction "K_2") (pintype "passive"))
      (node (ref "J7") (pin "10") (pinfunction "10_10") (pintype "passive"))
      (node (ref "Q2") (pin "2") (pinfunction "E_2") (pintype "passive"))
      (node (ref "Q3") (pin "2") (pinfunction "E_2") (pintype "passive"))
      (node (ref "Q4") (pin "2") (pinfunction "E_2") (pintype "passive"))
      (node (ref "Q5") (pin "2") (pinfunction "E_2") (pintype "passive"))
      (node (ref "Q6") (pin "2") (pinfunction "E_2") (pintype "passive"))
      (node (ref "Q7") (pin "2") (pinfunction "E_2") (pintype "passive"))
      (node (ref "Q8") (pin "2") (pinfunction "E_2") (pintype "passive"))
      (node (ref "Q9") (pin "2") (pinfunction "E_2") (pintype "passive"))
      (node (ref "R54") (pin "1") (pinfunction "1_1") (pintype "passive"))
      (node (ref "R55") (pin "1") (pinfunction "1_1") (pintype "passive"))
      (node (ref "R58") (pin "1") (pinfunction "1_1") (pintype "passive"))
      (node (ref "R59") (pin "1") (pinfunction "1_1") (pintype "passive"))
      (node (ref "R62") (pin "1") (pinfunction "1_1") (pintype "passive"))
      (node (ref "R63") (pin "1") (pinfunction "1_1") (pintype "passive"))
      (node (ref "R66") (pin "1") (pinfunction "1_1") (pintype "passive"))
      (node (ref "R67") (pin "1") (pinfunction "1_1") (pintype "passive"))
    )
    (net (code "188") (name "OCOM_P") (class "Default")
      (node (ref "D48") (pin "1") (pinfunction "A_1") (pintype "passive"))
      (node (ref "J7") (pin "1") (pinfunction "1_1") (pintype "passive"))
      (node (ref "U20") (pin "10") (pinfunction "C_10") (pintype "passive"))
      (node (ref "U20") (pin "12") (pinfunction "C_12") (pintype "passive"))
      (node (ref "U20") (pin "14") (pinfunction "C_14") (pintype "passive"))
      (node (ref "U20") (pin "16") (pinfunction "C_16") (pintype "passive"))
      (node (ref "U21") (pin "10") (pinfunction "C_10") (pintype "passive"))
      (node (ref "U21") (pin "12") (pinfunction "C_12") (pintype "passive"))
      (node (ref "U21") (pin "14") (pinfunction "C_14") (pintype "passive"))
      (node (ref "U21") (pin "16") (pinfunction "C_16") (pintype "passive"))
    )
    (net (code "189") (name "VBUS") (class "Default")
      (node (ref "D4") (pin "1") (pinfunction "A_1") (pintype "passive"))
      (node (ref "D7") (pin "1") (pinfunction "A_1") (pintype "passive"))
      (node (ref "J2") (pin "A4_B9") (pinfunction "VBUS_A4_B9") (pintype "power_in"))
      (node (ref "J2") (pin "B4_A9") (pinfunction "VBUS_B4_A9") (pintype "power_in"))
      (node (ref "U2") (pin "5") (pinfunction "VBUS_5") (pintype "power_in"))
    )
    (net (code "190") (name "unconnected-(J2-SBU1-PadA8)") (class "Default")
      (node (ref "J2") (pin "A8") (pinfunction "SBU1_A8") (pintype "passive"))
    )
    (net (code "191") (name "unconnected-(J2-SBU2-PadB8)") (class "Default")
      (node (ref "J2") (pin "B8") (pinfunction "SBU2_B8") (pintype "passive"))
    )
    (net (code "192") (name "unconnected-(J3-Pad1)") (class "Default")
      (node (ref "J3") (pin "1") (pinfunction "1_1") (pintype "passive"))
    )
    (net (code "193") (name "unconnected-(J3-Pad4)") (class "Default")
      (node (ref "J3") (pin "4") (pinfunction "4_4") (pintype "passive"))
    )
    (net (code "194") (name "unconnected-(J3-Pad6)") (class "Default")
      (node (ref "J3") (pin "6") (pinfunction "6_6") (pintype "passive"))
    )
    (net (code "195") (name "unconnected-(J3-Pad7)") (class "Default")
      (node (ref "J3") (pin "7") (pinfunction "7_7") (pintype "passive"))
    )
    (net (code "196") (name "unconnected-(J3-Pad8)") (class "Default")
      (node (ref "J3") (pin "8") (pinfunction "8_8") (pintype "passive"))
    )
    (net (code "197") (name "unconnected-(J3-Pad9)") (class "Default")
      (node (ref "J3") (pin "9") (pinfunction "9_9") (pintype "passive"))
    )
    (net (code "198") (name "unconnected-(J5-NC-Pad7)") (class "Default")
      (node (ref "J5") (pin "7") (pinfunction "NC_7") (pintype "passive"))
    )
    (net (code "199") (name "unconnected-(U3-PadEPAD)") (class "Default")
      (node (ref "U3") (pin "EPAD") (pinfunction "EPAD_EPAD") (pintype "power_in"))
    )
    (net (code "200") (name "unconnected-(U4-GND-Pad2)") (class "Default")
      (node (ref "U4") (pin "2") (pinfunction "GND_2") (pintype "power_in"))
    )
    (net (code "201") (name "unconnected-(U6-NC-Pad1)") (class "Default")
      (node (ref "U6") (pin "1") (pinfunction "NC_1") (pintype "passive"))
    )
    (net (code "202") (name "unconnected-(U6-NC-Pad4)") (class "Default")
      (node (ref "U6") (pin "4") (pinfunction "NC_4") (pintype "passive"))
    )
    (net (code "203") (name "unconnected-(U7-R2IN-Pad8)") (class "Default")
      (node (ref "U7") (pin "8") (pinfunction "R2IN_8") (pintype "input+no_connect"))
    )
    (net (code "204") (name "unconnected-(U7-R2OUT-Pad9)") (class "Default")
      (node (ref "U7") (pin "9") (pinfunction "R2OUT_9") (pintype "output+no_connect"))
    )
    (net (code "205") (name "unconnected-(U7-T2IN-Pad10)") (class "Default")
      (node (ref "U7") (pin "10") (pinfunction "T2IN_10") (pintype "input+no_connect"))
    )
    (net (code "206") (name "unconnected-(U7-T2OUT-Pad7)") (class "Default")
      (node (ref "U7") (pin "7") (pinfunction "T2OUT_7") (pintype "output"))
    )
    (net (code "207") (name "unconnected-(U8-NC-Pad1)") (class "Default")
      (node (ref "U8") (pin "1") (pinfunction "NC_1") (pintype "passive"))
    )
    (net (code "208") (name "unconnected-(U8-NC-Pad4)") (class "Default")
      (node (ref "U8") (pin "4") (pinfunction "NC_4") (pintype "passive"))
    )
    (net (code "209") (name "unconnected-(U11-NC-Pad1)") (class "Default")
      (node (ref "U11") (pin "1") (pinfunction "NC_1") (pintype "passive"))
    )
    (net (code "210") (name "unconnected-(U11-NC-Pad4)") (class "Default")
      (node (ref "U11") (pin "4") (pinfunction "NC_4") (pintype "passive"))
    )
    (net (code "211") (name "unconnected-(U12-NC-Pad1)") (class "Default")
      (node (ref "U12") (pin "1") (pinfunction "NC_1") (pintype "passive"))
    )
    (net (code "212") (name "unconnected-(U12-NC-Pad4)") (class "Default")
      (node (ref "U12") (pin "4") (pinfunction "NC_4") (pintype "passive"))
    )
    (net (code "213") (name "unconnected-(U13-NC-Pad1)") (class "Default")
      (node (ref "U13") (pin "1") (pinfunction "NC_1") (pintype "passive"))
    )
    (net (code "214") (name "unconnected-(U13-NC-Pad4)") (class "Default")
      (node (ref "U13") (pin "4") (pinfunction "NC_4") (pintype "passive"))
    )
    (net (code "215") (name "unconnected-(U14-CTS-Pad15)") (class "Default")
      (node (ref "U14") (pin "15") (pinfunction "CTS_15") (pintype "passive"))
    )
    (net (code "216") (name "unconnected-(U14-RTS{slash}TNOW1-Pad16)") (class "Default")
      (node (ref "U14") (pin "16") (pinfunction "RTS/TNOW1_16") (pintype "passive"))
    )
    (net (code "217") (name "unconnected-(U14-RXD2-Pad10)") (class "Default")
      (node (ref "U14") (pin "10") (pinfunction "RXD2_10") (pintype "passive"))
    )
    (net (code "218") (name "unconnected-(U14-TNOW2-Pad12)") (class "Default")
      (node (ref "U14") (pin "12") (pinfunction "TNOW2_12") (pintype "passive"))
    )
    (net (code "219") (name "unconnected-(U14-TXD2-Pad9)") (class "Default")
      (node (ref "U14") (pin "9") (pinfunction "TXD2_9") (pintype "passive"))
    )
    (net (code "220") (name "unconnected-(U15-IO35-Pad28)") (class "Default")
      (node (ref "U15") (pin "28") (pinfunction "IO35_28") (pintype "bidirectional"))
    )
    (net (code "221") (name "unconnected-(U15-IO36-Pad29)") (class "Default")
      (node (ref "U15") (pin "29") (pinfunction "IO36_29") (pintype "bidirectional"))
    )
    (net (code "222") (name "unconnected-(U15-IO37-Pad30)") (class "Default")
      (node (ref "U15") (pin "30") (pinfunction "IO37_30") (pintype "bidirectional"))
    )
    (net (code "223") (name "unconnected-(U18-+-Pad1)") (class "Default")
      (node (ref "U18") (pin "1") (pinfunction "+_1") (pintype "passive"))
    )
    (net (code "224") (name "unconnected-(U18-+-Pad3)") (class "Default")
      (node (ref "U18") (pin "3") (pinfunction "+_3") (pintype "passive"))
    )
    (net (code "225") (name "unconnected-(U18---Pad2)") (class "Default")
      (node (ref "U18") (pin "2") (pinfunction "-_2") (pintype "passive"))
    )
    (net (code "226") (name "unconnected-(U18---Pad4)") (class "Default")
      (node (ref "U18") (pin "4") (pinfunction "-_4") (pintype "passive"))
    )
    (net (code "227") (name "unconnected-(U18-C-Pad14)") (class "Default")
      (node (ref "U18") (pin "14") (pinfunction "C_14") (pintype "passive"))
    )
    (net (code "228") (name "unconnected-(U18-C-Pad16)") (class "Default")
      (node (ref "U18") (pin "16") (pinfunction "C_16") (pintype "passive"))
    )
    (net (code "229") (name "unconnected-(U18-E-Pad13)") (class "Default")
      (node (ref "U18") (pin "13") (pinfunction "E_13") (pintype "passive"))
    )
    (net (code "230") (name "unconnected-(U18-E-Pad15)") (class "Default")
      (node (ref "U18") (pin "15") (pinfunction "E_15") (pintype "passive"))
    )
    (net (code "231") (name "unconnected-(U19-+-Pad1)") (class "Default")
      (node (ref "U19") (pin "1") (pinfunction "+_1") (pintype "passive"))
    )
    (net (code "232") (name "unconnected-(U19-+-Pad3)") (class "Default")
      (node (ref "U19") (pin "3") (pinfunction "+_3") (pintype "passive"))
    )
    (net (code "233") (name "unconnected-(U19---Pad2)") (class "Default")
      (node (ref "U19") (pin "2") (pinfunction "-_2") (pintype "passive"))
    )
    (net (code "234") (name "unconnected-(U19---Pad4)") (class "Default")
      (node (ref "U19") (pin "4") (pinfunction "-_4") (pintype "passive"))
    )
    (net (code "235") (name "unconnected-(U19-C-Pad14)") (class "Default")
      (node (ref "U19") (pin "14") (pinfunction "C_14") (pintype "passive"))
    )
    (net (code "236") (name "unconnected-(U19-C-Pad16)") (class "Default")
      (node (ref "U19") (pin "16") (pinfunction "C_16") (pintype "passive"))
    )
    (net (code "237") (name "unconnected-(U19-E-Pad13)") (class "Default")
      (node (ref "U19") (pin "13") (pinfunction "E_13") (pintype "passive"))
    )
    (net (code "238") (name "unconnected-(U19-E-Pad15)") (class "Default")
      (node (ref "U19") (pin "15") (pinfunction "E_15") (pintype "passive"))
    )
  )
)
